# FastDataAcq.net
KiCad netlist of a schematic drawn in EAGLE
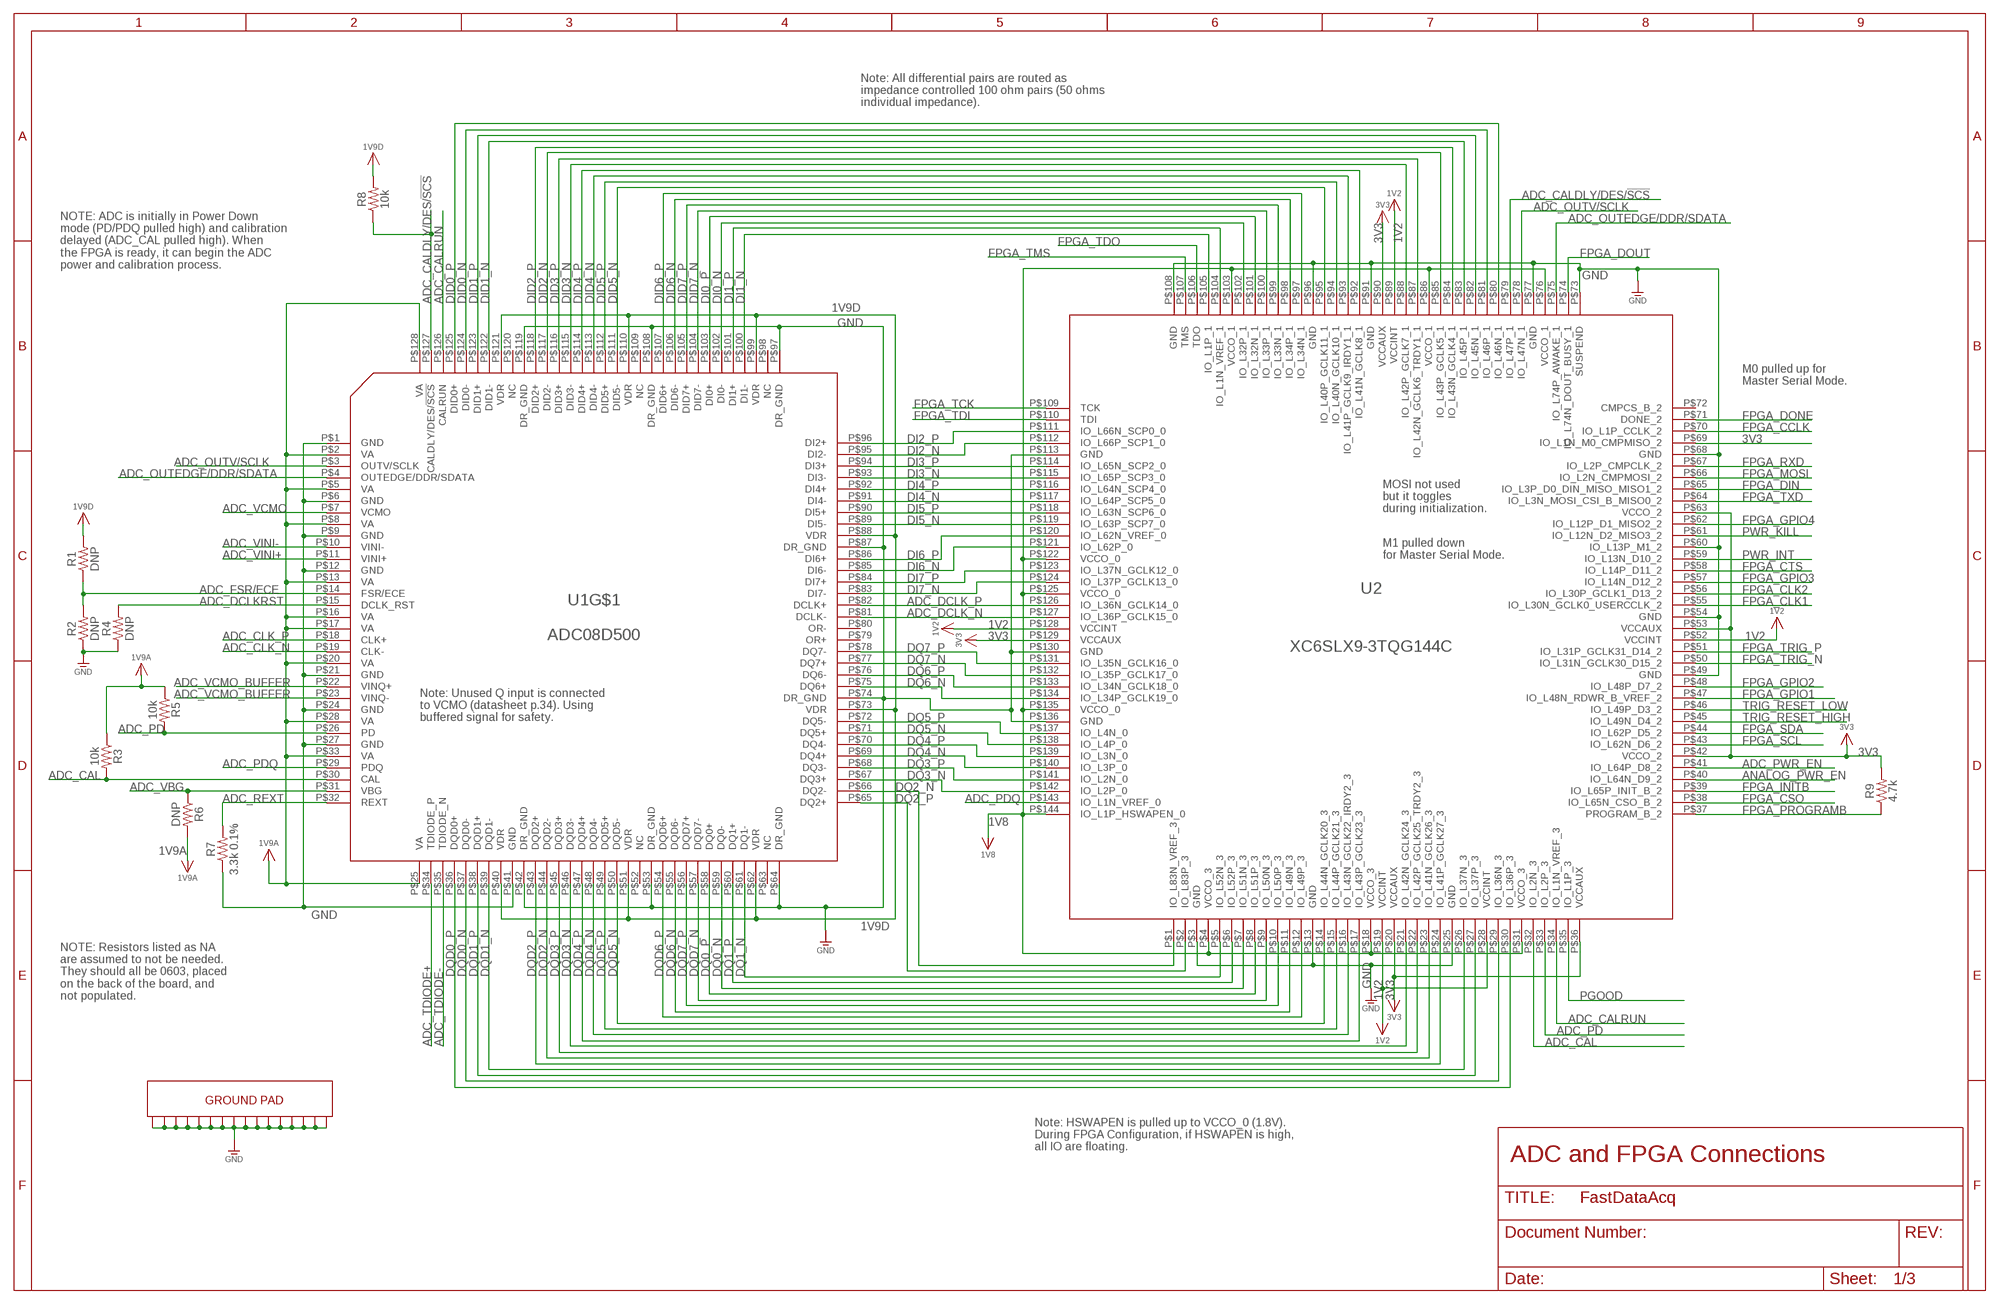
[diagram p0: schematic, sheet 1]
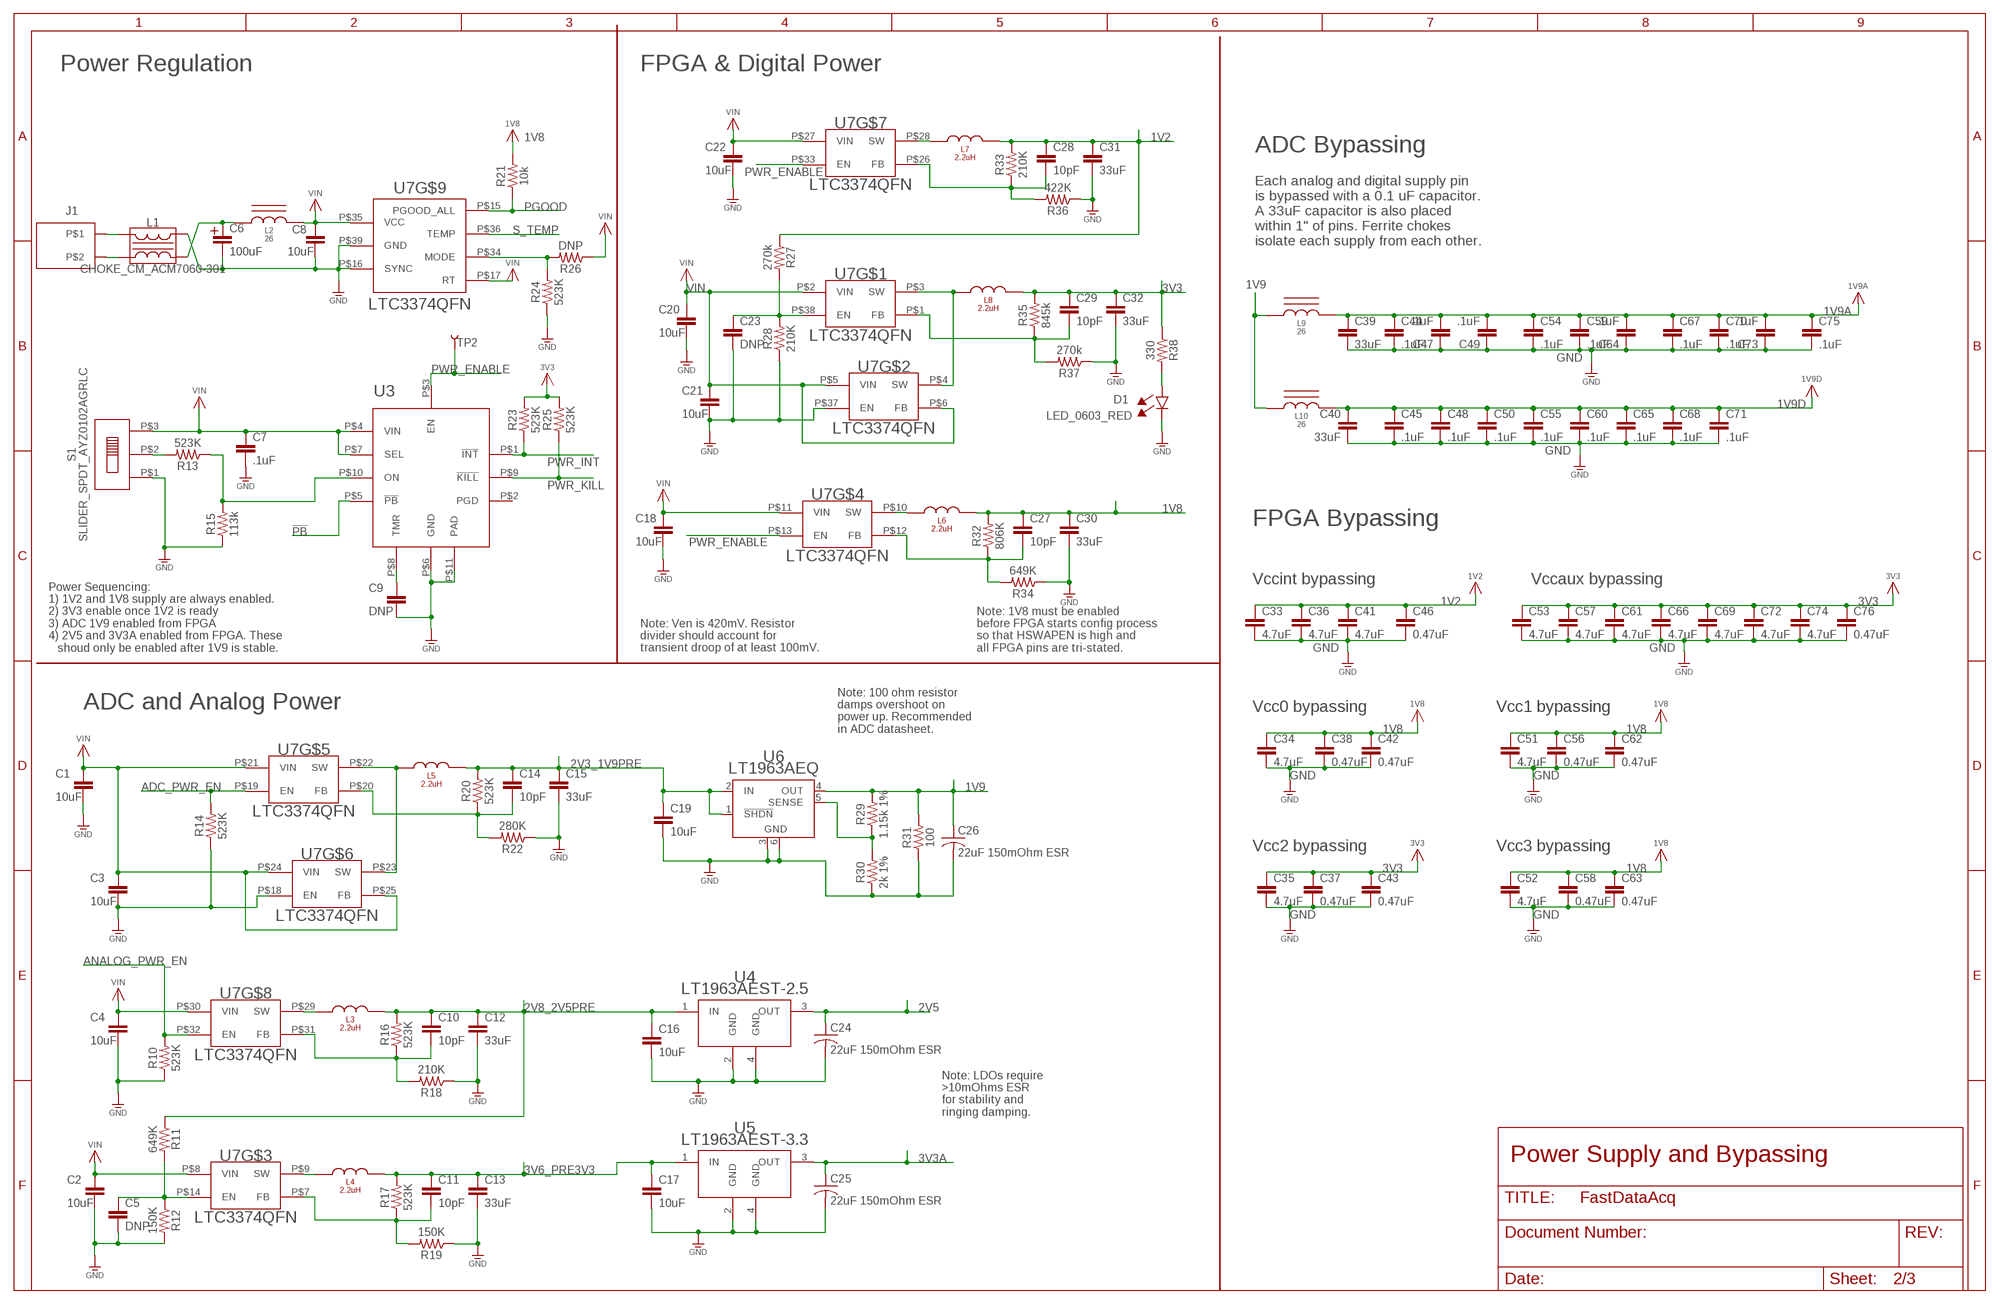
[diagram p1: schematic, sheet 2]
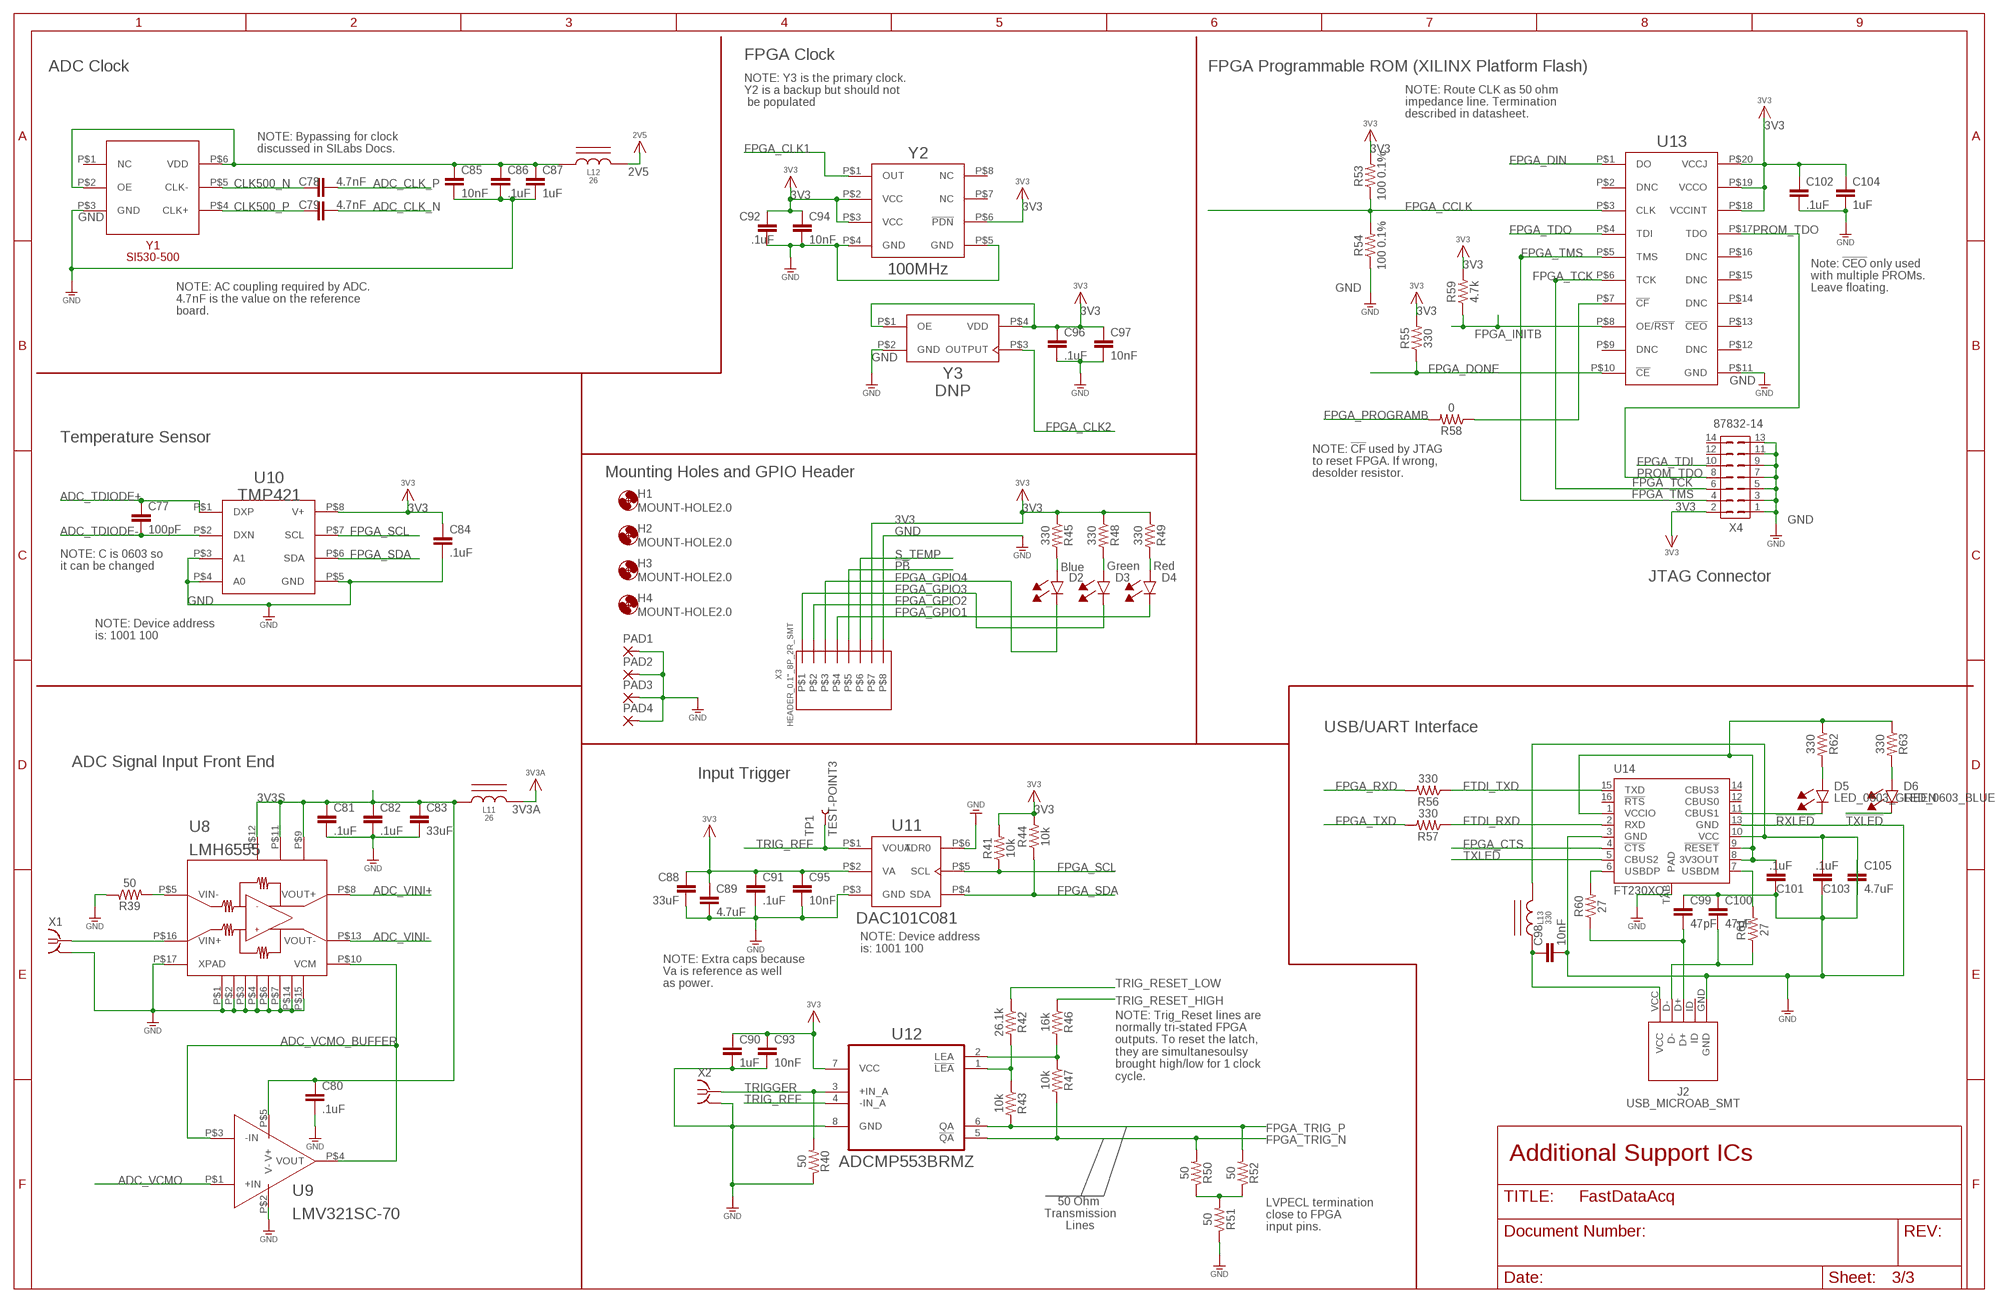
[diagram p2: schematic, sheet 3]

(export (version "E")
  (design (tool "Eeschema 10.0.6"))
  (components
    (comp (ref "R1")
      (value "DNP")
      (footprint "eagle-import:R0603")
      (libsource (lib "eagle-import") (part "R-US_R0603"))
    )
    (comp (ref "R2")
      (value "DNP")
      (footprint "eagle-import:R0603")
      (libsource (lib "eagle-import") (part "R-US_R0603"))
    )
    (comp (ref "R3")
      (value "10k")
      (footprint "eagle-import:R0201")
      (fields
        (field (name "MANPARTNUMBER") "RC0603J103CS")
        (field (name "MANUFACTURER") "Samsung Electro-Mechanics America, Inc")
        (field (name "PARTNUMBER") "1276-3817-1-ND")
      )
      (libsource (lib "eagle-import") (part "R-US_R0201"))
    )
    (comp (ref "R4")
      (value "DNP")
      (footprint "eagle-import:R0603")
      (libsource (lib "eagle-import") (part "R-US_R0603"))
    )
    (comp (ref "R5")
      (value "10k")
      (footprint "eagle-import:R0201")
      (fields
        (field (name "MANPARTNUMBER") "RC0603J103CS")
        (field (name "MANUFACTURER") "Samsung Electro-Mechanics America, Inc")
        (field (name "PARTNUMBER") "1276-3817-1-ND")
      )
      (libsource (lib "eagle-import") (part "R-US_R0201"))
    )
    (comp (ref "R6")
      (value "DNP")
      (footprint "eagle-import:R0603")
      (libsource (lib "eagle-import") (part "R-US_R0603"))
    )
    (comp (ref "R7")
      (value "3.3k 0.1%")
      (footprint "eagle-import:R0603")
      (fields (field (name "PARTNUMBER") "P3.3KDBCT-ND"))
      (libsource (lib "eagle-import") (part "R-US_R0603"))
    )
    (comp (ref "R8")
      (value "10k")
      (footprint "eagle-import:R0201")
      (fields
        (field (name "MANPARTNUMBER") "RC0603J103CS")
        (field (name "MANUFACTURER") "Samsung Electro-Mechanics America, Inc")
        (field (name "PARTNUMBER") "1276-3817-1-ND")
      )
      (libsource (lib "eagle-import") (part "R-US_R0201"))
    )
    (comp (ref "R9")
      (value "4.7k")
      (footprint "eagle-import:R0201")
      (fields
        (field (name "MANPARTNUMBER") "ERJ-1GNJ472C")
        (field (name "MANUFACTURER") "Panasonic Electronic Components")
        (field (name "PARTNUMBER") "P4.7AECT-ND")
      )
      (libsource (lib "eagle-import") (part "R-US_R0201"))
    )
    (comp (ref "U1")
      (value "ADC08D500")
      (footprint "eagle-import:128HLQFP")
      (fields
        (field (name "MANPARTNUMBER") "ADC08D500CIYB/NOPB")
        (field (name "MANUFACTURER") "Texas Instruments")
        (field (name "PARTNUMBER") "ADC08D500CIYB/NOPB-ND")
        (field (name "PARTNUMBER_1") "ADC08D500CIYB/NOPB-ND")
        (field (name "SUPPLIER") "DIGIKEY")
      )
      (libsource (lib "eagle-import") (part "ADC08D500"))
    )
    (comp (ref "U2")
      (value "XC6SLX9-3TQG144C")
      (footprint "eagle-import:TQG144")
      (fields (field (name "MANUFACTURER") "Xilinx Inc") (field (name "PARTNUMBER") "122-1747-ND"))
      (libsource (lib "eagle-import") (part "XC6SLX9-3TQG144C"))
    )
    (comp (ref "C1")
      (value "10uF")
      (footprint "eagle-import:C0603")
      (fields (field (name "PARTNUMBER") "445-4112-1-ND"))
      (libsource (lib "eagle-import") (part "C-EUC0603"))
    )
    (comp (ref "C2")
      (value "10uF")
      (footprint "eagle-import:C0603")
      (fields (field (name "PARTNUMBER") "445-4112-1-ND"))
      (libsource (lib "eagle-import") (part "C-EUC0603"))
    )
    (comp (ref "C3")
      (value "10uF")
      (footprint "eagle-import:C0603")
      (fields (field (name "PARTNUMBER") "445-4112-1-ND"))
      (libsource (lib "eagle-import") (part "C-EUC0603"))
    )
    (comp (ref "C4")
      (value "10uF")
      (footprint "eagle-import:C0603")
      (fields (field (name "PARTNUMBER") "445-4112-1-ND"))
      (libsource (lib "eagle-import") (part "C-EUC0603"))
    )
    (comp (ref "C5")
      (value "DNP")
      (footprint "eagle-import:C0603")
      (libsource (lib "eagle-import") (part "C-EUC0603"))
    )
    (comp (ref "C6")
      (value "100uF")
      (footprint "eagle-import:2917_MURATA_CAP")
      (fields
        (field (name "MANUFACTURER") "Murata Electronics North America")
        (field (name "MANPARTNUMBER") "ECASD91B107M012K00")
        (field (name "PARTNUMBER") "490-5480-1-ND")
      )
      (libsource (lib "eagle-import") (part "CAP_POL_D9_SERIES"))
    )
    (comp (ref "C7")
      (value ".1uF")
      (footprint "eagle-import:0204REVERSE")
      (fields (field (name "PARTNUMBER") "587-2152-1-ND") (field (name "SUPPLIER") "DIGIKEY"))
      (libsource (lib "eagle-import") (part "CAPACITOR0204_REVERSE"))
    )
    (comp (ref "C8")
      (value "10uF")
      (footprint "eagle-import:C0603")
      (fields (field (name "PARTNUMBER") "445-4112-1-ND"))
      (libsource (lib "eagle-import") (part "C-EUC0603"))
    )
    (comp (ref "C9")
      (value "DNP")
      (footprint "eagle-import:C0603")
      (libsource (lib "eagle-import") (part "C-EUC0603"))
    )
    (comp (ref "C10")
      (value "10pF")
      (footprint "eagle-import:C0201")
      (fields (field (name "PARTNUMBER") "445-1769-1-ND"))
      (libsource (lib "eagle-import") (part "C-EUC0201"))
    )
    (comp (ref "C11")
      (value "10pF")
      (footprint "eagle-import:C0201")
      (fields (field (name "PARTNUMBER") "445-1769-1-ND"))
      (libsource (lib "eagle-import") (part "C-EUC0201"))
    )
    (comp (ref "C12")
      (value "33uF")
      (footprint "eagle-import:0805")
      (fields (field (name "PARTNUMBER") "445-8238-1-ND"))
      (libsource (lib "eagle-import") (part "CAP0805"))
    )
    (comp (ref "C13")
      (value "33uF")
      (footprint "eagle-import:0805")
      (fields (field (name "PARTNUMBER") "445-8238-1-ND"))
      (libsource (lib "eagle-import") (part "CAP0805"))
    )
    (comp (ref "C14")
      (value "10pF")
      (footprint "eagle-import:C0201")
      (fields (field (name "PARTNUMBER") "445-1769-1-ND"))
      (libsource (lib "eagle-import") (part "C-EUC0201"))
    )
    (comp (ref "C15")
      (value "33uF")
      (footprint "eagle-import:0805")
      (fields (field (name "PARTNUMBER") "445-8238-1-ND"))
      (libsource (lib "eagle-import") (part "CAP0805"))
    )
    (comp (ref "C16")
      (value "10uF")
      (footprint "eagle-import:C0603")
      (fields (field (name "PARTNUMBER") "445-4112-1-ND"))
      (libsource (lib "eagle-import") (part "C-EUC0603"))
    )
    (comp (ref "C17")
      (value "10uF")
      (footprint "eagle-import:C0603")
      (fields (field (name "PARTNUMBER") "445-4112-1-ND"))
      (libsource (lib "eagle-import") (part "C-EUC0603"))
    )
    (comp (ref "C18")
      (value "10uF")
      (footprint "eagle-import:C0603")
      (fields (field (name "PARTNUMBER") "445-4112-1-ND"))
      (libsource (lib "eagle-import") (part "C-EUC0603"))
    )
    (comp (ref "C19")
      (value "10uF")
      (footprint "eagle-import:C0603")
      (fields (field (name "PARTNUMBER") "445-4112-1-ND"))
      (libsource (lib "eagle-import") (part "C-EUC0603"))
    )
    (comp (ref "C20")
      (value "10uF")
      (footprint "eagle-import:C0603")
      (fields (field (name "PARTNUMBER") "445-4112-1-ND"))
      (libsource (lib "eagle-import") (part "C-EUC0603"))
    )
    (comp (ref "C21")
      (value "10uF")
      (footprint "eagle-import:C0603")
      (fields (field (name "PARTNUMBER") "445-4112-1-ND"))
      (libsource (lib "eagle-import") (part "C-EUC0603"))
    )
    (comp (ref "C22")
      (value "10uF")
      (footprint "eagle-import:C0603")
      (fields (field (name "PARTNUMBER") "445-4112-1-ND"))
      (libsource (lib "eagle-import") (part "C-EUC0603"))
    )
    (comp (ref "C23")
      (value "DNP")
      (footprint "eagle-import:C0603")
      (libsource (lib "eagle-import") (part "C-EUC0603"))
    )
    (comp (ref "C24")
      (value "22uF 150mOhm ESR")
      (footprint "eagle-import:C0805")
      (fields (field (name "PARTNUMBER") "P16231CT-ND"))
      (libsource (lib "eagle-import") (part "C-USC0805"))
    )
    (comp (ref "C25")
      (value "22uF 150mOhm ESR")
      (footprint "eagle-import:C0805")
      (fields (field (name "PARTNUMBER") "P16231CT-ND"))
      (libsource (lib "eagle-import") (part "C-USC0805"))
    )
    (comp (ref "C26")
      (value "22uF 150mOhm ESR")
      (footprint "eagle-import:C0805")
      (fields (field (name "PARTNUMBER") "P16231CT-ND"))
      (libsource (lib "eagle-import") (part "C-USC0805"))
    )
    (comp (ref "C27")
      (value "10pF")
      (footprint "eagle-import:C0201")
      (fields (field (name "PARTNUMBER") "445-1769-1-ND"))
      (libsource (lib "eagle-import") (part "C-EUC0201"))
    )
    (comp (ref "C28")
      (value "10pF")
      (footprint "eagle-import:C0201")
      (fields (field (name "PARTNUMBER") "445-1769-1-ND"))
      (libsource (lib "eagle-import") (part "C-EUC0201"))
    )
    (comp (ref "C29")
      (value "10pF")
      (footprint "eagle-import:C0201")
      (fields (field (name "PARTNUMBER") "445-1769-1-ND"))
      (libsource (lib "eagle-import") (part "C-EUC0201"))
    )
    (comp (ref "C30")
      (value "33uF")
      (footprint "eagle-import:0805")
      (fields (field (name "PARTNUMBER") "445-8238-1-ND"))
      (libsource (lib "eagle-import") (part "CAP0805"))
    )
    (comp (ref "C31")
      (value "33uF")
      (footprint "eagle-import:0805")
      (fields (field (name "PARTNUMBER") "445-8238-1-ND"))
      (libsource (lib "eagle-import") (part "CAP0805"))
    )
    (comp (ref "C32")
      (value "33uF")
      (footprint "eagle-import:0805")
      (fields (field (name "PARTNUMBER") "445-8238-1-ND"))
      (libsource (lib "eagle-import") (part "CAP0805"))
    )
    (comp (ref "C33")
      (value "4.7uF")
      (footprint "eagle-import:0402_C")
      (fields
        (field (name "MANPARTNUMBER") "CL05A475MQ5NRNC")
        (field (name "MANUFACTURER") "Samsung Electro-Mechanics America, Inc")
        (field (name "PARTNUMBER") "1276-1056-1-ND")
      )
      (libsource (lib "eagle-import") (part "CAPACITOR"))
    )
    (comp (ref "C34")
      (value "4.7uF")
      (footprint "eagle-import:0402_C")
      (fields
        (field (name "MANPARTNUMBER") "CL05A475MQ5NRNC")
        (field (name "MANUFACTURER") "Samsung Electro-Mechanics America, Inc")
        (field (name "PARTNUMBER") "1276-1056-1-ND")
      )
      (libsource (lib "eagle-import") (part "CAPACITOR"))
    )
    (comp (ref "C35")
      (value "4.7uF")
      (footprint "eagle-import:0402_C")
      (fields
        (field (name "MANPARTNUMBER") "CL05A475MQ5NRNC")
        (field (name "MANUFACTURER") "Samsung Electro-Mechanics America, Inc")
        (field (name "PARTNUMBER") "1276-1056-1-ND")
      )
      (libsource (lib "eagle-import") (part "CAPACITOR"))
    )
    (comp (ref "C36")
      (value "4.7uF")
      (footprint "eagle-import:0402_C")
      (fields
        (field (name "MANPARTNUMBER") "CL05A475MQ5NRNC")
        (field (name "MANUFACTURER") "Samsung Electro-Mechanics America, Inc")
        (field (name "PARTNUMBER") "1276-1056-1-ND")
      )
      (libsource (lib "eagle-import") (part "CAPACITOR"))
    )
    (comp (ref "C37")
      (value "0.47uF")
      (footprint "eagle-import:0204REVERSE")
      (fields (field (name "PARTNUMBER") "1276-1779-1-ND") (field (name "SUPPLIER") "DIGIKEY"))
      (libsource (lib "eagle-import") (part "CAPACITOR0204_REVERSE"))
    )
    (comp (ref "C38")
      (value "0.47uF")
      (footprint "eagle-import:0204REVERSE")
      (fields (field (name "PARTNUMBER") "1276-1779-1-ND") (field (name "SUPPLIER") "DIGIKEY"))
      (libsource (lib "eagle-import") (part "CAPACITOR0204_REVERSE"))
    )
    (comp (ref "C39")
      (value "33uF")
      (footprint "eagle-import:0805")
      (fields (field (name "PARTNUMBER") "445-8238-1-ND"))
      (libsource (lib "eagle-import") (part "CAP0805"))
    )
    (comp (ref "C40")
      (value "33uF")
      (footprint "eagle-import:0805")
      (fields (field (name "PARTNUMBER") "445-8238-1-ND"))
      (libsource (lib "eagle-import") (part "CAP0805"))
    )
    (comp (ref "C41")
      (value "4.7uF")
      (footprint "eagle-import:0402_C")
      (fields
        (field (name "MANPARTNUMBER") "CL05A475MQ5NRNC")
        (field (name "MANUFACTURER") "Samsung Electro-Mechanics America, Inc")
        (field (name "PARTNUMBER") "1276-1056-1-ND")
      )
      (libsource (lib "eagle-import") (part "CAPACITOR"))
    )
    (comp (ref "C42")
      (value "0.47uF")
      (footprint "eagle-import:0204REVERSE")
      (fields (field (name "PARTNUMBER") "1276-1779-1-ND") (field (name "SUPPLIER") "DIGIKEY"))
      (libsource (lib "eagle-import") (part "CAPACITOR0204_REVERSE"))
    )
    (comp (ref "C43")
      (value "0.47uF")
      (footprint "eagle-import:0204REVERSE")
      (fields (field (name "PARTNUMBER") "1276-1779-1-ND") (field (name "SUPPLIER") "DIGIKEY"))
      (libsource (lib "eagle-import") (part "CAPACITOR0204_REVERSE"))
    )
    (comp (ref "C44")
      (value ".1uF")
      (footprint "eagle-import:0204REVERSE")
      (fields (field (name "PARTNUMBER") "587-2152-1-ND") (field (name "SUPPLIER") "DIGIKEY"))
      (libsource (lib "eagle-import") (part "CAPACITOR0204_REVERSE"))
    )
    (comp (ref "C45")
      (value ".1uF")
      (footprint "eagle-import:0204REVERSE")
      (fields (field (name "PARTNUMBER") "587-2152-1-ND") (field (name "SUPPLIER") "DIGIKEY"))
      (libsource (lib "eagle-import") (part "CAPACITOR0204_REVERSE"))
    )
    (comp (ref "C46")
      (value "0.47uF")
      (footprint "eagle-import:0204REVERSE")
      (fields (field (name "PARTNUMBER") "1276-1779-1-ND") (field (name "SUPPLIER") "DIGIKEY"))
      (libsource (lib "eagle-import") (part "CAPACITOR0204_REVERSE"))
    )
    (comp (ref "C47")
      (value ".1uF")
      (footprint "eagle-import:0204REVERSE")
      (fields (field (name "PARTNUMBER") "587-2152-1-ND") (field (name "SUPPLIER") "DIGIKEY"))
      (libsource (lib "eagle-import") (part "CAPACITOR0204_REVERSE"))
    )
    (comp (ref "C48")
      (value ".1uF")
      (footprint "eagle-import:0204REVERSE")
      (fields (field (name "PARTNUMBER") "587-2152-1-ND") (field (name "SUPPLIER") "DIGIKEY"))
      (libsource (lib "eagle-import") (part "CAPACITOR0204_REVERSE"))
    )
    (comp (ref "C49")
      (value ".1uF")
      (footprint "eagle-import:0204REVERSE")
      (fields (field (name "PARTNUMBER") "587-2152-1-ND") (field (name "SUPPLIER") "DIGIKEY"))
      (libsource (lib "eagle-import") (part "CAPACITOR0204_REVERSE"))
    )
    (comp (ref "C50")
      (value ".1uF")
      (footprint "eagle-import:0204REVERSE")
      (fields (field (name "PARTNUMBER") "587-2152-1-ND") (field (name "SUPPLIER") "DIGIKEY"))
      (libsource (lib "eagle-import") (part "CAPACITOR0204_REVERSE"))
    )
    (comp (ref "C51")
      (value "4.7uF")
      (footprint "eagle-import:0402_C")
      (fields
        (field (name "MANPARTNUMBER") "CL05A475MQ5NRNC")
        (field (name "MANUFACTURER") "Samsung Electro-Mechanics America, Inc")
        (field (name "PARTNUMBER") "1276-1056-1-ND")
      )
      (libsource (lib "eagle-import") (part "CAPACITOR"))
    )
    (comp (ref "C52")
      (value "4.7uF")
      (footprint "eagle-import:0402_C")
      (fields
        (field (name "MANPARTNUMBER") "CL05A475MQ5NRNC")
        (field (name "MANUFACTURER") "Samsung Electro-Mechanics America, Inc")
        (field (name "PARTNUMBER") "1276-1056-1-ND")
      )
      (libsource (lib "eagle-import") (part "CAPACITOR"))
    )
    (comp (ref "C53")
      (value "4.7uF")
      (footprint "eagle-import:0402_C")
      (fields
        (field (name "MANPARTNUMBER") "CL05A475MQ5NRNC")
        (field (name "MANUFACTURER") "Samsung Electro-Mechanics America, Inc")
        (field (name "PARTNUMBER") "1276-1056-1-ND")
      )
      (libsource (lib "eagle-import") (part "CAPACITOR"))
    )
    (comp (ref "C54")
      (value ".1uF")
      (footprint "eagle-import:0204REVERSE")
      (fields (field (name "PARTNUMBER") "587-2152-1-ND") (field (name "SUPPLIER") "DIGIKEY"))
      (libsource (lib "eagle-import") (part "CAPACITOR0204_REVERSE"))
    )
    (comp (ref "C55")
      (value ".1uF")
      (footprint "eagle-import:0204REVERSE")
      (fields (field (name "PARTNUMBER") "587-2152-1-ND") (field (name "SUPPLIER") "DIGIKEY"))
      (libsource (lib "eagle-import") (part "CAPACITOR0204_REVERSE"))
    )
    (comp (ref "C56")
      (value "0.47uF")
      (footprint "eagle-import:0204REVERSE")
      (fields (field (name "PARTNUMBER") "1276-1779-1-ND") (field (name "SUPPLIER") "DIGIKEY"))
      (libsource (lib "eagle-import") (part "CAPACITOR0204_REVERSE"))
    )
    (comp (ref "C57")
      (value "4.7uF")
      (footprint "eagle-import:0402_C")
      (fields
        (field (name "MANPARTNUMBER") "CL05A475MQ5NRNC")
        (field (name "MANUFACTURER") "Samsung Electro-Mechanics America, Inc")
        (field (name "PARTNUMBER") "1276-1056-1-ND")
      )
      (libsource (lib "eagle-import") (part "CAPACITOR"))
    )
    (comp (ref "C58")
      (value "0.47uF")
      (footprint "eagle-import:0204REVERSE")
      (fields (field (name "PARTNUMBER") "1276-1779-1-ND") (field (name "SUPPLIER") "DIGIKEY"))
      (libsource (lib "eagle-import") (part "CAPACITOR0204_REVERSE"))
    )
    (comp (ref "C59")
      (value ".1uF")
      (footprint "eagle-import:0204REVERSE")
      (fields (field (name "PARTNUMBER") "587-2152-1-ND") (field (name "SUPPLIER") "DIGIKEY"))
      (libsource (lib "eagle-import") (part "CAPACITOR0204_REVERSE"))
    )
    (comp (ref "C60")
      (value ".1uF")
      (footprint "eagle-import:0204REVERSE")
      (fields (field (name "PARTNUMBER") "587-2152-1-ND") (field (name "SUPPLIER") "DIGIKEY"))
      (libsource (lib "eagle-import") (part "CAPACITOR0204_REVERSE"))
    )
    (comp (ref "C61")
      (value "4.7uF")
      (footprint "eagle-import:0402_C")
      (fields
        (field (name "MANPARTNUMBER") "CL05A475MQ5NRNC")
        (field (name "MANUFACTURER") "Samsung Electro-Mechanics America, Inc")
        (field (name "PARTNUMBER") "1276-1056-1-ND")
      )
      (libsource (lib "eagle-import") (part "CAPACITOR"))
    )
    (comp (ref "C62")
      (value "0.47uF")
      (footprint "eagle-import:0204REVERSE")
      (fields (field (name "PARTNUMBER") "1276-1779-1-ND") (field (name "SUPPLIER") "DIGIKEY"))
      (libsource (lib "eagle-import") (part "CAPACITOR0204_REVERSE"))
    )
    (comp (ref "C63")
      (value "0.47uF")
      (footprint "eagle-import:0204REVERSE")
      (fields (field (name "PARTNUMBER") "1276-1779-1-ND") (field (name "SUPPLIER") "DIGIKEY"))
      (libsource (lib "eagle-import") (part "CAPACITOR0204_REVERSE"))
    )
    (comp (ref "C64")
      (value ".1uF")
      (footprint "eagle-import:0204REVERSE")
      (fields (field (name "PARTNUMBER") "587-2152-1-ND") (field (name "SUPPLIER") "DIGIKEY"))
      (libsource (lib "eagle-import") (part "CAPACITOR0204_REVERSE"))
    )
    (comp (ref "C65")
      (value ".1uF")
      (footprint "eagle-import:0204REVERSE")
      (fields (field (name "PARTNUMBER") "587-2152-1-ND") (field (name "SUPPLIER") "DIGIKEY"))
      (libsource (lib "eagle-import") (part "CAPACITOR0204_REVERSE"))
    )
    (comp (ref "C66")
      (value "4.7uF")
      (footprint "eagle-import:0402_C")
      (fields
        (field (name "MANPARTNUMBER") "CL05A475MQ5NRNC")
        (field (name "MANUFACTURER") "Samsung Electro-Mechanics America, Inc")
        (field (name "PARTNUMBER") "1276-1056-1-ND")
      )
      (libsource (lib "eagle-import") (part "CAPACITOR"))
    )
    (comp (ref "C67")
      (value ".1uF")
      (footprint "eagle-import:0204REVERSE")
      (fields (field (name "PARTNUMBER") "587-2152-1-ND") (field (name "SUPPLIER") "DIGIKEY"))
      (libsource (lib "eagle-import") (part "CAPACITOR0204_REVERSE"))
    )
    (comp (ref "C68")
      (value ".1uF")
      (footprint "eagle-import:0204REVERSE")
      (fields (field (name "PARTNUMBER") "587-2152-1-ND") (field (name "SUPPLIER") "DIGIKEY"))
      (libsource (lib "eagle-import") (part "CAPACITOR0204_REVERSE"))
    )
    (comp (ref "C69")
      (value "4.7uF")
      (footprint "eagle-import:0402_C")
      (fields
        (field (name "MANPARTNUMBER") "CL05A475MQ5NRNC")
        (field (name "MANUFACTURER") "Samsung Electro-Mechanics America, Inc")
        (field (name "PARTNUMBER") "1276-1056-1-ND")
      )
      (libsource (lib "eagle-import") (part "CAPACITOR"))
    )
    (comp (ref "C70")
      (value ".1uF")
      (footprint "eagle-import:0204REVERSE")
      (fields (field (name "PARTNUMBER") "587-2152-1-ND") (field (name "SUPPLIER") "DIGIKEY"))
      (libsource (lib "eagle-import") (part "CAPACITOR0204_REVERSE"))
    )
    (comp (ref "C71")
      (value ".1uF")
      (footprint "eagle-import:0204REVERSE")
      (fields (field (name "PARTNUMBER") "587-2152-1-ND") (field (name "SUPPLIER") "DIGIKEY"))
      (libsource (lib "eagle-import") (part "CAPACITOR0204_REVERSE"))
    )
    (comp (ref "C72")
      (value "4.7uF")
      (footprint "eagle-import:0402_C")
      (fields
        (field (name "MANPARTNUMBER") "CL05A475MQ5NRNC")
        (field (name "MANUFACTURER") "Samsung Electro-Mechanics America, Inc")
        (field (name "PARTNUMBER") "1276-1056-1-ND")
      )
      (libsource (lib "eagle-import") (part "CAPACITOR"))
    )
    (comp (ref "C73")
      (value ".1uF")
      (footprint "eagle-import:0204REVERSE")
      (fields (field (name "PARTNUMBER") "587-2152-1-ND") (field (name "SUPPLIER") "DIGIKEY"))
      (libsource (lib "eagle-import") (part "CAPACITOR0204_REVERSE"))
    )
    (comp (ref "C74")
      (value "4.7uF")
      (footprint "eagle-import:0402_C")
      (fields
        (field (name "MANPARTNUMBER") "CL05A475MQ5NRNC")
        (field (name "MANUFACTURER") "Samsung Electro-Mechanics America, Inc")
        (field (name "PARTNUMBER") "1276-1056-1-ND")
      )
      (libsource (lib "eagle-import") (part "CAPACITOR"))
    )
    (comp (ref "C75")
      (value ".1uF")
      (footprint "eagle-import:0204REVERSE")
      (fields (field (name "PARTNUMBER") "587-2152-1-ND") (field (name "SUPPLIER") "DIGIKEY"))
      (libsource (lib "eagle-import") (part "CAPACITOR0204_REVERSE"))
    )
    (comp (ref "C76")
      (value "0.47uF")
      (footprint "eagle-import:0204REVERSE")
      (fields (field (name "PARTNUMBER") "1276-1779-1-ND") (field (name "SUPPLIER") "DIGIKEY"))
      (libsource (lib "eagle-import") (part "CAPACITOR0204_REVERSE"))
    )
    (comp (ref "D1")
      (value "LED_0603_RED")
      (footprint "eagle-import:0603_LED")
      (fields
        (field (name "MANPARTNUMBER") "LTST-C193KRKT-5A")
        (field (name "MANUFACTURER") "Lite-On Inc")
        (field (name "PARTNUMBER") "160-1830-1-ND")
        (field (name "PARTNUMBER_1") "LNJ237W82RACT-ND")
      )
      (libsource (lib "eagle-import") (part "LED_0603_RED"))
    )
    (comp (ref "J1")
      (value "MICRO-FIT_3.0_2POS_RA_SMD")
      (footprint "eagle-import:MICRO-FIT_3.02POS_RA_SMD")
      (fields
        (field (name "MANPARTNUMBER") "0436500212")
        (field (name "MANUFACTURER") "Molex Inc")
        (field (name "PARTNUMBER") "WM1890CT-ND")
      )
      (libsource (lib "eagle-import") (part "MICRO-FIT_3.0_2POS_RA_SMD"))
    )
    (comp (ref "L1")
      (value "CHOKE_CM_ACM7060-301")
      (footprint "eagle-import:ACM7060_CHOKE")
      (fields
        (field (name "MANPARTNUMBER") "ACM7060-301-2PL-TL01")
        (field (name "MANUFACTURER") "TDK Corporation")
        (field (name "PARTNUMBER") "445-2214-1-ND")
      )
      (libsource (lib "eagle-import") (part "CHOKE_CM_ACM7060-301"))
    )
    (comp (ref "L2")
      (value "26")
      (footprint "eagle-import:MURATA_BLM18")
      (fields
        (field (name "MANPARTNUMBER") "BLM18SG260TN1D")
        (field (name "MANUFACTURER") "Murata Electronics North America")
        (field (name "PARTNUMBER") "490-3995-1-ND")
      )
      (libsource (lib "eagle-import") (part "FERRITE_BEADS_BLM18SG260"))
    )
    (comp (ref "L3")
      (value "2.2uH")
      (footprint "eagle-import:3.0X3.6_VISHAY")
      (fields (field (name "PARTNUMBER") "541-1322-1-ND") (field (name "SUPPLIER") "DIGIKEY"))
      (libsource (lib "eagle-import") (part "INDUCTOR_3X3.6"))
    )
    (comp (ref "L4")
      (value "2.2uH")
      (footprint "eagle-import:3.0X3.6_VISHAY")
      (fields (field (name "PARTNUMBER") "541-1322-1-ND") (field (name "SUPPLIER") "DIGIKEY"))
      (libsource (lib "eagle-import") (part "INDUCTOR_3X3.6"))
    )
    (comp (ref "L5")
      (value "2.2uH")
      (footprint "eagle-import:5.18X5.49_VISHAY")
      (fields (field (name "PARTNUMBER") "541-1220-1-ND") (field (name "SUPPLIER") "DIGIKEY"))
      (libsource (lib "eagle-import") (part "INDUCTOR_5.18X5.49"))
    )
    (comp (ref "L6")
      (value "2.2uH")
      (footprint "eagle-import:3.0X3.6_VISHAY")
      (fields (field (name "PARTNUMBER") "541-1322-1-ND") (field (name "SUPPLIER") "DIGIKEY"))
      (libsource (lib "eagle-import") (part "INDUCTOR_3X3.6"))
    )
    (comp (ref "L7")
      (value "2.2uH")
      (footprint "eagle-import:3.0X3.6_VISHAY")
      (fields (field (name "PARTNUMBER") "541-1322-1-ND") (field (name "SUPPLIER") "DIGIKEY"))
      (libsource (lib "eagle-import") (part "INDUCTOR_3X3.6"))
    )
    (comp (ref "L8")
      (value "2.2uH")
      (footprint "eagle-import:5.18X5.49_VISHAY")
      (fields (field (name "PARTNUMBER") "541-1220-1-ND") (field (name "SUPPLIER") "DIGIKEY"))
      (libsource (lib "eagle-import") (part "INDUCTOR_5.18X5.49"))
    )
    (comp (ref "L9")
      (value "26")
      (footprint "eagle-import:MURATA_BLM18")
      (fields
        (field (name "MANPARTNUMBER") "BLM18SG260TN1D")
        (field (name "MANUFACTURER") "Murata Electronics North America")
        (field (name "PARTNUMBER") "490-3995-1-ND")
      )
      (libsource (lib "eagle-import") (part "FERRITE_BEADS_BLM18SG260"))
    )
    (comp (ref "L10")
      (value "26")
      (footprint "eagle-import:MURATA_BLM18")
      (fields
        (field (name "MANPARTNUMBER") "BLM18SG260TN1D")
        (field (name "MANUFACTURER") "Murata Electronics North America")
        (field (name "PARTNUMBER") "490-3995-1-ND")
      )
      (libsource (lib "eagle-import") (part "FERRITE_BEADS_BLM18SG260"))
    )
    (comp (ref "R10")
      (value "523K")
      (footprint "eagle-import:R0201")
      (fields (field (name "PARTNUMBER") "P523KABCT-ND"))
      (libsource (lib "eagle-import") (part "R-US_R0201"))
    )
    (comp (ref "R11")
      (value "649K")
      (footprint "eagle-import:R0201")
      (fields (field (name "PARTNUMBER") "P649KABCT-ND"))
      (libsource (lib "eagle-import") (part "R-US_R0201"))
    )
    (comp (ref "R12")
      (value "150K")
      (footprint "eagle-import:R0201")
      (fields (field (name "PARTNUMBER") "1276-3719-1-ND"))
      (libsource (lib "eagle-import") (part "R-US_R0201"))
    )
    (comp (ref "R13")
      (value "523K")
      (footprint "eagle-import:R0201")
      (fields (field (name "PARTNUMBER") "P523KABCT-ND"))
      (libsource (lib "eagle-import") (part "R-US_R0201"))
    )
    (comp (ref "R14")
      (value "523K")
      (footprint "eagle-import:R0201")
      (fields (field (name "PARTNUMBER") "P523KABCT-ND"))
      (libsource (lib "eagle-import") (part "R-US_R0201"))
    )
    (comp (ref "R15")
      (value "113k")
      (footprint "eagle-import:R0201")
      (fields (field (name "PARTNUMBER") "P113KABCT-ND"))
      (libsource (lib "eagle-import") (part "R-US_R0201"))
    )
    (comp (ref "R16")
      (value "523K")
      (footprint "eagle-import:R0201")
      (fields (field (name "PARTNUMBER") "P523KABCT-ND"))
      (libsource (lib "eagle-import") (part "R-US_R0201"))
    )
    (comp (ref "R17")
      (value "523K")
      (footprint "eagle-import:R0201")
      (fields (field (name "PARTNUMBER") "P523KABCT-ND"))
      (libsource (lib "eagle-import") (part "R-US_R0201"))
    )
    (comp (ref "R18")
      (value "210K")
      (footprint "eagle-import:R0201")
      (fields (field (name "PARTNUMBER") "P210KABCT-ND"))
      (libsource (lib "eagle-import") (part "R-US_R0201"))
    )
    (comp (ref "R19")
      (value "150K")
      (footprint "eagle-import:R0201")
      (fields (field (name "PARTNUMBER") "1276-3719-1-ND"))
      (libsource (lib "eagle-import") (part "R-US_R0201"))
    )
    (comp (ref "R20")
      (value "523K")
      (footprint "eagle-import:R0201")
      (fields (field (name "PARTNUMBER") "P523KABCT-ND"))
      (libsource (lib "eagle-import") (part "R-US_R0201"))
    )
    (comp (ref "R21")
      (value "10k")
      (footprint "eagle-import:R0201")
      (fields
        (field (name "MANPARTNUMBER") "RC0603J103CS")
        (field (name "MANUFACTURER") "Samsung Electro-Mechanics America, Inc")
        (field (name "PARTNUMBER") "1276-3817-1-ND")
      )
      (libsource (lib "eagle-import") (part "R-US_R0201"))
    )
    (comp (ref "R22")
      (value "280K")
      (footprint "eagle-import:R0201")
      (fields (field (name "PARTNUMBER") "P280KABCT-ND"))
      (libsource (lib "eagle-import") (part "R-US_R0201"))
    )
    (comp (ref "R23")
      (value "523K")
      (footprint "eagle-import:R0201")
      (fields (field (name "PARTNUMBER") "P523KABCT-ND"))
      (libsource (lib "eagle-import") (part "R-US_R0201"))
    )
    (comp (ref "R24")
      (value "523K")
      (footprint "eagle-import:R0201")
      (fields (field (name "PARTNUMBER") "P523KABCT-ND"))
      (libsource (lib "eagle-import") (part "R-US_R0201"))
    )
    (comp (ref "R25")
      (value "523K")
      (footprint "eagle-import:R0201")
      (fields (field (name "PARTNUMBER") "P523KABCT-ND"))
      (libsource (lib "eagle-import") (part "R-US_R0201"))
    )
    (comp (ref "R26")
      (value "DNP")
      (footprint "eagle-import:R0603")
      (libsource (lib "eagle-import") (part "R-US_R0603"))
    )
    (comp (ref "R27")
      (value "270k")
      (footprint "eagle-import:R0201")
      (fields (field (name "PARTNUMBER") "P270KABCT-ND"))
      (libsource (lib "eagle-import") (part "R-US_R0201"))
    )
    (comp (ref "R28")
      (value "210K")
      (footprint "eagle-import:R0201")
      (fields (field (name "PARTNUMBER") "P210KABCT-ND"))
      (libsource (lib "eagle-import") (part "R-US_R0201"))
    )
    (comp (ref "R29")
      (value "1.15k 1%")
      (footprint "eagle-import:R0603")
      (fields
        (field (name "MANPARTNUMBER") "RC1608F1151CS")
        (field (name "MANUFACTURER") "Samsung Electro-Mechanics America, Inc")
        (field (name "PARTNUMBER") "1276-4649-1-ND")
      )
      (libsource (lib "eagle-import") (part "R-US_R0603"))
    )
    (comp (ref "R30")
      (value "2k 1%")
      (footprint "eagle-import:R0603")
      (fields
        (field (name "MANPARTNUMBER") "RC1608F202CS")
        (field (name "MANUFACTURER") "Samsung Electro-Mechanics America, Inc")
        (field (name "PARTNUMBER") "1276-3495-1-ND")
      )
      (libsource (lib "eagle-import") (part "R-US_R0603"))
    )
    (comp (ref "R31")
      (value "100")
      (footprint "eagle-import:R0603")
      (fields
        (field (name "MANPARTNUMBER") "RC1608J101CS")
        (field (name "MANUFACTURER") "Samsung Electro-Mechanics America, Inc")
        (field (name "PARTNUMBER") "1276-5038-1-ND")
      )
      (libsource (lib "eagle-import") (part "R-US_R0603"))
    )
    (comp (ref "R32")
      (value "806K")
      (footprint "eagle-import:R0201")
      (fields (field (name "PARTNUMBER") "P806KABCT-ND"))
      (libsource (lib "eagle-import") (part "R-US_R0201"))
    )
    (comp (ref "R33")
      (value "210K")
      (footprint "eagle-import:R0201")
      (fields (field (name "PARTNUMBER") "P210KABCT-ND"))
      (libsource (lib "eagle-import") (part "R-US_R0201"))
    )
    (comp (ref "R34")
      (value "649K")
      (footprint "eagle-import:R0201")
      (fields (field (name "PARTNUMBER") "P649KABCT-ND"))
      (libsource (lib "eagle-import") (part "R-US_R0201"))
    )
    (comp (ref "R35")
      (value "845k")
      (footprint "eagle-import:R0201")
      (fields (field (name "PARTNUMBER") "P845KABCT-ND"))
      (libsource (lib "eagle-import") (part "R-US_R0201"))
    )
    (comp (ref "R36")
      (value "422K")
      (footprint "eagle-import:R0201")
      (fields (field (name "PARTNUMBER") "P442KABCT-ND"))
      (libsource (lib "eagle-import") (part "R-US_R0201"))
    )
    (comp (ref "R37")
      (value "270k")
      (footprint "eagle-import:R0201")
      (fields (field (name "PARTNUMBER") "P270KABCT-ND"))
      (libsource (lib "eagle-import") (part "R-US_R0201"))
    )
    (comp (ref "R38")
      (value "330")
      (footprint "eagle-import:R0201")
      (fields
        (field (name "MANPARTNUMBER") "RC0603J331CS")
        (field (name "MANUFACTURER") "Samsung Electro-Mechanics America, Inc")
        (field (name "PARTNUMBER") "1276-3787-1-ND")
      )
      (libsource (lib "eagle-import") (part "R-US_R0201"))
    )
    (comp (ref "S1")
      (value "SLIDER_SPDT_AYZ0102AGRLC")
      (footprint "eagle-import:AYZ0102AGRLC")
      (fields
        (field (name "MANPARTNUMBER") "AYZ0102AGRLC")
        (field (name "MANUFACTURER") "C&K Components")
        (field (name "PARTNUMBER") "401-2012-1-ND")
      )
      (libsource (lib "eagle-import") (part "SLIDER_SPDT_AYZ0102AGRLC"))
    )
    (comp (ref "TP2")
      (value "TEST-POINT3")
      (footprint "eagle-import:PAD.03X.03")
      (libsource (lib "eagle-import") (part "TEST-POINT3"))
    )
    (comp (ref "U3")
      (value "LTC2955-1")
      (footprint "eagle-import:10-DFN")
      (fields
        (field (name "MANPARTNUMBER") "LTC2955CDDB-1#TRMPBF")
        (field (name "MANUFACTURER") "Linear Technology")
        (field (name "PARTNUMBER") "LTC2955CDDB-1#TRMPBFCT-ND")
      )
      (libsource (lib "eagle-import") (part "LTC2955-1"))
    )
    (comp (ref "U4")
      (value "LT1963AEST-2.5")
      (footprint "eagle-import:SOT223")
      (fields
        (field (name "MANPARTNUMBER") "LT1963AEST-2.5#PBF")
        (field (name "MANUFACTURER") "Linear Technology")
        (field (name "PARTNUMBER") "LT1963AEST-2.5#PBF-ND")
      )
      (libsource (lib "eagle-import") (part "LT1963AEST-2.5"))
    )
    (comp (ref "U5")
      (value "LT1963AEST-3.3")
      (footprint "eagle-import:SOT223")
      (fields
        (field (name "MANPARTNUMBER") "LT1963AEST-3.3#PBF")
        (field (name "MANUFACTURER") "Linear Technology")
        (field (name "PARTNUMBER") "LT1963AEST-3.3#PBF-ND")
      )
      (libsource (lib "eagle-import") (part "LT1963AEST-3.3"))
    )
    (comp (ref "U6")
      (value "LT1963AEQ")
      (footprint "eagle-import:Q5-DD")
      (fields
        (field (name "MANPARTNUMBER") "LT1963AEQ#PBF")
        (field (name "MANUFACTURER") "Linear Technology")
        (field (name "PARTNUMBER") "LT1963AEQ#PBF-ND")
      )
      (libsource (lib "eagle-import") (part "LT1963AEQ"))
    )
    (comp (ref "U7")
      (value "LTC3374QFN")
      (footprint "eagle-import:38-QFN_(5X7)")
      (fields
        (field (name "MANPARTNUMBER") "TC3374EUHF#PBF")
        (field (name "MANUFACTURER") "Linear Technology")
        (field (name "PARTNUMBER") "LTC3374EUHF#PBF-ND")
      )
      (libsource (lib "eagle-import") (part "LTC3374QFN"))
    )
    (comp (ref "C77")
      (value "100pF")
      (footprint "eagle-import:C0201")
      (fields (field (name "PARTNUMBER") "445-4675-1-ND") (field (name "SUPPLIER") "DIGIKEY"))
      (libsource (lib "eagle-import") (part "C-EUC0201"))
    )
    (comp (ref "C78")
      (value "4.7nF")
      (footprint "eagle-import:C0201")
      (fields (field (name "PARTNUMBER") "445-13726-1-ND"))
      (libsource (lib "eagle-import") (part "C-EUC0201"))
    )
    (comp (ref "C79")
      (value "4.7nF")
      (footprint "eagle-import:C0201")
      (fields (field (name "PARTNUMBER") "445-13726-1-ND"))
      (libsource (lib "eagle-import") (part "C-EUC0201"))
    )
    (comp (ref "C80")
      (value ".1uF")
      (footprint "eagle-import:0204REVERSE")
      (fields (field (name "PARTNUMBER") "587-2152-1-ND") (field (name "SUPPLIER") "DIGIKEY"))
      (libsource (lib "eagle-import") (part "CAPACITOR0204_REVERSE"))
    )
    (comp (ref "C81")
      (value ".1uF")
      (footprint "eagle-import:0204REVERSE")
      (fields (field (name "PARTNUMBER") "587-2152-1-ND") (field (name "SUPPLIER") "DIGIKEY"))
      (libsource (lib "eagle-import") (part "CAPACITOR0204_REVERSE"))
    )
    (comp (ref "C82")
      (value ".1uF")
      (footprint "eagle-import:0204REVERSE")
      (fields (field (name "PARTNUMBER") "587-2152-1-ND") (field (name "SUPPLIER") "DIGIKEY"))
      (libsource (lib "eagle-import") (part "CAPACITOR0204_REVERSE"))
    )
    (comp (ref "C83")
      (value "33uF")
      (footprint "eagle-import:0805")
      (fields (field (name "PARTNUMBER") "445-8238-1-ND"))
      (libsource (lib "eagle-import") (part "CAP0805"))
    )
    (comp (ref "C84")
      (value ".1uF")
      (footprint "eagle-import:0204REVERSE")
      (fields (field (name "PARTNUMBER") "587-2152-1-ND") (field (name "SUPPLIER") "DIGIKEY"))
      (libsource (lib "eagle-import") (part "CAPACITOR0204_REVERSE"))
    )
    (comp (ref "C85")
      (value "10nF")
      (footprint "eagle-import:C0201")
      (fields (field (name "PARTNUMBER") "445-1793-1-ND"))
      (libsource (lib "eagle-import") (part "C-EUC0201"))
    )
    (comp (ref "C86")
      (value ".1uF")
      (footprint "eagle-import:0204REVERSE")
      (fields (field (name "PARTNUMBER") "587-2152-1-ND") (field (name "SUPPLIER") "DIGIKEY"))
      (libsource (lib "eagle-import") (part "CAPACITOR0204_REVERSE"))
    )
    (comp (ref "C87")
      (value "1uF")
      (footprint "eagle-import:0204REVERSE")
      (fields (field (name "PARTNUMBER") "445-9091-1-ND") (field (name "SUPPLIER") "DIGIKEY"))
      (libsource (lib "eagle-import") (part "CAPACITOR0204_REVERSE"))
    )
    (comp (ref "C88")
      (value "33uF")
      (footprint "eagle-import:0805")
      (fields (field (name "PARTNUMBER") "445-8238-1-ND"))
      (libsource (lib "eagle-import") (part "CAP0805"))
    )
    (comp (ref "C89")
      (value "4.7uF")
      (footprint "eagle-import:0402_C")
      (fields
        (field (name "MANPARTNUMBER") "CL05A475MQ5NRNC")
        (field (name "MANUFACTURER") "Samsung Electro-Mechanics America, Inc")
        (field (name "PARTNUMBER") "1276-1056-1-ND")
      )
      (libsource (lib "eagle-import") (part "CAPACITOR"))
    )
    (comp (ref "C90")
      (value "1uF")
      (footprint "eagle-import:0204REVERSE")
      (fields (field (name "PARTNUMBER") "445-9091-1-ND") (field (name "SUPPLIER") "DIGIKEY"))
      (libsource (lib "eagle-import") (part "CAPACITOR0204_REVERSE"))
    )
    (comp (ref "C91")
      (value ".1uF")
      (footprint "eagle-import:0204REVERSE")
      (fields (field (name "PARTNUMBER") "587-2152-1-ND") (field (name "SUPPLIER") "DIGIKEY"))
      (libsource (lib "eagle-import") (part "CAPACITOR0204_REVERSE"))
    )
    (comp (ref "C92")
      (value ".1uF")
      (footprint "eagle-import:0204REVERSE")
      (fields (field (name "PARTNUMBER") "587-2152-1-ND") (field (name "SUPPLIER") "DIGIKEY"))
      (libsource (lib "eagle-import") (part "CAPACITOR0204_REVERSE"))
    )
    (comp (ref "C93")
      (value "10nF")
      (footprint "eagle-import:C0201")
      (fields (field (name "PARTNUMBER") "445-1793-1-ND"))
      (libsource (lib "eagle-import") (part "C-EUC0201"))
    )
    (comp (ref "C94")
      (value "10nF")
      (footprint "eagle-import:C0201")
      (fields (field (name "PARTNUMBER") "445-1793-1-ND"))
      (libsource (lib "eagle-import") (part "C-EUC0201"))
    )
    (comp (ref "C95")
      (value "10nF")
      (footprint "eagle-import:C0201")
      (fields (field (name "PARTNUMBER") "445-1793-1-ND"))
      (libsource (lib "eagle-import") (part "C-EUC0201"))
    )
    (comp (ref "C96")
      (value ".1uF")
      (footprint "eagle-import:0204REVERSE")
      (fields (field (name "PARTNUMBER") "587-2152-1-ND") (field (name "SUPPLIER") "DIGIKEY"))
      (libsource (lib "eagle-import") (part "CAPACITOR0204_REVERSE"))
    )
    (comp (ref "C97")
      (value "10nF")
      (footprint "eagle-import:C0201")
      (fields (field (name "PARTNUMBER") "445-1793-1-ND"))
      (libsource (lib "eagle-import") (part "C-EUC0201"))
    )
    (comp (ref "C98")
      (value "10nF")
      (footprint "eagle-import:C0201")
      (fields (field (name "PARTNUMBER") "445-1793-1-ND"))
      (libsource (lib "eagle-import") (part "C-EUC0201"))
    )
    (comp (ref "C99")
      (value "47pF")
      (footprint "eagle-import:C0201")
      (fields (field (name "PARTNUMBER") "445-1782-1-ND"))
      (libsource (lib "eagle-import") (part "C-EUC0201"))
    )
    (comp (ref "C100")
      (value "47pF")
      (footprint "eagle-import:C0201")
      (fields (field (name "PARTNUMBER") "445-1782-1-ND"))
      (libsource (lib "eagle-import") (part "C-EUC0201"))
    )
    (comp (ref "C101")
      (value ".1uF")
      (footprint "eagle-import:0204REVERSE")
      (fields (field (name "PARTNUMBER") "587-2152-1-ND") (field (name "SUPPLIER") "DIGIKEY"))
      (libsource (lib "eagle-import") (part "CAPACITOR0204_REVERSE"))
    )
    (comp (ref "C102")
      (value ".1uF")
      (footprint "eagle-import:0204REVERSE")
      (fields (field (name "PARTNUMBER") "587-2152-1-ND") (field (name "SUPPLIER") "DIGIKEY"))
      (libsource (lib "eagle-import") (part "CAPACITOR0204_REVERSE"))
    )
    (comp (ref "C103")
      (value ".1uF")
      (footprint "eagle-import:0204REVERSE")
      (fields (field (name "PARTNUMBER") "587-2152-1-ND") (field (name "SUPPLIER") "DIGIKEY"))
      (libsource (lib "eagle-import") (part "CAPACITOR0204_REVERSE"))
    )
    (comp (ref "C104")
      (value "1uF")
      (footprint "eagle-import:0204REVERSE")
      (fields (field (name "PARTNUMBER") "445-9091-1-ND") (field (name "SUPPLIER") "DIGIKEY"))
      (libsource (lib "eagle-import") (part "CAPACITOR0204_REVERSE"))
    )
    (comp (ref "C105")
      (value "4.7uF")
      (footprint "eagle-import:0402_C")
      (fields
        (field (name "MANPARTNUMBER") "CL05A475MQ5NRNC")
        (field (name "MANUFACTURER") "Samsung Electro-Mechanics America, Inc")
        (field (name "PARTNUMBER") "1276-1056-1-ND")
      )
      (libsource (lib "eagle-import") (part "CAPACITOR"))
    )
    (comp (ref "D2")
      (value "LED_0603_BLUE")
      (footprint "eagle-import:0603_LED")
      (fields
        (field (name "MANPARTNUMBER") "LTST-C193TBKT-5A")
        (field (name "MANUFACTURER") "Lite-On Inc")
        (field (name "PARTNUMBER") "160-1827-1-ND")
      )
      (libsource (lib "eagle-import") (part "LED_0603_BLUE"))
    )
    (comp (ref "D3")
      (value "LED_0603_GREEN")
      (footprint "eagle-import:0603_LED")
      (fields
        (field (name "MANPARTNUMBER") "LTST-C193KGKT-5A")
        (field (name "MANUFACTURER") "Lite-On Inc")
        (field (name "PARTNUMBER") "160-1828-1-ND")
      )
      (libsource (lib "eagle-import") (part "LED_0603_GREEN"))
    )
    (comp (ref "D4")
      (value "LED_0603_RED")
      (footprint "eagle-import:0603_LED")
      (fields
        (field (name "MANPARTNUMBER") "LTST-C193KRKT-5A")
        (field (name "MANUFACTURER") "Lite-On Inc")
        (field (name "PARTNUMBER") "160-1830-1-ND")
        (field (name "PARTNUMBER_1") "LNJ237W82RACT-ND")
      )
      (libsource (lib "eagle-import") (part "LED_0603_RED"))
    )
    (comp (ref "D5")
      (value "LED_0603_GREEN")
      (footprint "eagle-import:0603_LED")
      (fields
        (field (name "MANPARTNUMBER") "LTST-C193KGKT-5A")
        (field (name "MANUFACTURER") "Lite-On Inc")
        (field (name "PARTNUMBER") "160-1828-1-ND")
      )
      (libsource (lib "eagle-import") (part "LED_0603_GREEN"))
    )
    (comp (ref "D6")
      (value "LED_0603_BLUE")
      (footprint "eagle-import:0603_LED")
      (fields
        (field (name "MANPARTNUMBER") "LTST-C193TBKT-5A")
        (field (name "MANUFACTURER") "Lite-On Inc")
        (field (name "PARTNUMBER") "160-1827-1-ND")
      )
      (libsource (lib "eagle-import") (part "LED_0603_BLUE"))
    )
    (comp (ref "H1")
      (value "MOUNT-HOLE2.0")
      (footprint "eagle-import:2.0")
      (libsource (lib "eagle-import") (part "MOUNT-HOLE2.0"))
    )
    (comp (ref "H2")
      (value "MOUNT-HOLE2.0")
      (footprint "eagle-import:2.0")
      (libsource (lib "eagle-import") (part "MOUNT-HOLE2.0"))
    )
    (comp (ref "H3")
      (value "MOUNT-HOLE2.0")
      (footprint "eagle-import:2.0")
      (libsource (lib "eagle-import") (part "MOUNT-HOLE2.0"))
    )
    (comp (ref "H4")
      (value "MOUNT-HOLE2.0")
      (footprint "eagle-import:2.0")
      (libsource (lib "eagle-import") (part "MOUNT-HOLE2.0"))
    )
    (comp (ref "J2")
      (value "USB_MICROAB_SMT")
      (footprint "eagle-import:USB_MICROAB_SMT_1")
      (fields
        (field (name "MANPARTNUMBER") "10104111-0001LF")
        (field (name "MANUFACTURER") "FCI")
        (field (name "PARTNUMBER") "609-4053-1-ND")
      )
      (libsource (lib "eagle-import") (part "USB_MICROAB_SMT"))
    )
    (comp (ref "L11")
      (value "26")
      (footprint "eagle-import:MURATA_BLM18")
      (fields
        (field (name "MANPARTNUMBER") "BLM18SG260TN1D")
        (field (name "MANUFACTURER") "Murata Electronics North America")
        (field (name "PARTNUMBER") "490-3995-1-ND")
      )
      (libsource (lib "eagle-import") (part "FERRITE_BEADS_BLM18SG260"))
    )
    (comp (ref "L12")
      (value "26")
      (footprint "eagle-import:MURATA_BLM18")
      (fields
        (field (name "MANPARTNUMBER") "BLM18SG260TN1D")
        (field (name "MANUFACTURER") "Murata Electronics North America")
        (field (name "PARTNUMBER") "490-3995-1-ND")
      )
      (libsource (lib "eagle-import") (part "FERRITE_BEADS_BLM18SG260"))
    )
    (comp (ref "L13")
      (value "330")
      (footprint "eagle-import:MURATA_BLM18")
      (fields
        (field (name "MANPARTNUMBER") "BLM18SG331TN1D")
        (field (name "MANUFACTURER") "Murata Electronics North America")
        (field (name "PARTNUMBER") "490-3997-1-ND")
      )
      (libsource (lib "eagle-import") (part "FERRITE_BEADS_BLM18SG331"))
    )
    (comp (ref "PAD1")
      (value "SMD2")
      (footprint "eagle-import:SMD1,27-2,54")
      (libsource (lib "eagle-import") (part "SMD2"))
    )
    (comp (ref "PAD2")
      (value "SMD2")
      (footprint "eagle-import:SMD1,27-2,54")
      (libsource (lib "eagle-import") (part "SMD2"))
    )
    (comp (ref "PAD3")
      (value "SMD2")
      (footprint "eagle-import:SMD1,27-2,54")
      (libsource (lib "eagle-import") (part "SMD2"))
    )
    (comp (ref "PAD4")
      (value "SMD2")
      (footprint "eagle-import:SMD1,27-2,54")
      (libsource (lib "eagle-import") (part "SMD2"))
    )
    (comp (ref "R39")
      (value "50")
      (footprint "eagle-import:R0201")
      (fields
        (field (name "MANPARTNUMBER") "RC0603F49R9C")
        (field (name "MANUFACTURER") "Samsung Electro-Mechanics America, Inc")
        (field (name "PARTNUMBER") "1276-3590-1-ND")
      )
      (libsource (lib "eagle-import") (part "R-US_R0201"))
    )
    (comp (ref "R40")
      (value "50")
      (footprint "eagle-import:R0201")
      (fields
        (field (name "MANPARTNUMBER") "RC0603F49R9C")
        (field (name "MANUFACTURER") "Samsung Electro-Mechanics America, Inc")
        (field (name "PARTNUMBER") "1276-3590-1-ND")
      )
      (libsource (lib "eagle-import") (part "R-US_R0201"))
    )
    (comp (ref "R41")
      (value "10k")
      (footprint "eagle-import:R0201")
      (fields
        (field (name "MANPARTNUMBER") "RC0603J103CS")
        (field (name "MANUFACTURER") "Samsung Electro-Mechanics America, Inc")
        (field (name "PARTNUMBER") "1276-3817-1-ND")
      )
      (libsource (lib "eagle-import") (part "R-US_R0201"))
    )
    (comp (ref "R42")
      (value "26.1k")
      (footprint "eagle-import:R0603")
      (fields (field (name "PARTNUMBER") "1276-4779-1-ND"))
      (libsource (lib "eagle-import") (part "R-US_R0603"))
    )
    (comp (ref "R43")
      (value "10k")
      (footprint "eagle-import:R0201")
      (fields
        (field (name "MANPARTNUMBER") "RC0603J103CS")
        (field (name "MANUFACTURER") "Samsung Electro-Mechanics America, Inc")
        (field (name "PARTNUMBER") "1276-3817-1-ND")
      )
      (libsource (lib "eagle-import") (part "R-US_R0201"))
    )
    (comp (ref "R44")
      (value "10k")
      (footprint "eagle-import:R0201")
      (fields
        (field (name "MANPARTNUMBER") "RC0603J103CS")
        (field (name "MANUFACTURER") "Samsung Electro-Mechanics America, Inc")
        (field (name "PARTNUMBER") "1276-3817-1-ND")
      )
      (libsource (lib "eagle-import") (part "R-US_R0201"))
    )
    (comp (ref "R45")
      (value "330")
      (footprint "eagle-import:R0201")
      (fields
        (field (name "MANPARTNUMBER") "RC0603J331CS")
        (field (name "MANUFACTURER") "Samsung Electro-Mechanics America, Inc")
        (field (name "PARTNUMBER") "1276-3787-1-ND")
      )
      (libsource (lib "eagle-import") (part "R-US_R0201"))
    )
    (comp (ref "R46")
      (value "16k")
      (footprint "eagle-import:R0603")
      (fields (field (name "PARTNUMBER") "1276-5091-1-ND"))
      (libsource (lib "eagle-import") (part "R-US_R0603"))
    )
    (comp (ref "R47")
      (value "10k")
      (footprint "eagle-import:R0201")
      (fields
        (field (name "MANPARTNUMBER") "RC0603J103CS")
        (field (name "MANUFACTURER") "Samsung Electro-Mechanics America, Inc")
        (field (name "PARTNUMBER") "1276-3817-1-ND")
      )
      (libsource (lib "eagle-import") (part "R-US_R0201"))
    )
    (comp (ref "R48")
      (value "330")
      (footprint "eagle-import:R0201")
      (fields
        (field (name "MANPARTNUMBER") "RC0603J331CS")
        (field (name "MANUFACTURER") "Samsung Electro-Mechanics America, Inc")
        (field (name "PARTNUMBER") "1276-3787-1-ND")
      )
      (libsource (lib "eagle-import") (part "R-US_R0201"))
    )
    (comp (ref "R49")
      (value "330")
      (footprint "eagle-import:R0201")
      (fields
        (field (name "MANPARTNUMBER") "RC0603J331CS")
        (field (name "MANUFACTURER") "Samsung Electro-Mechanics America, Inc")
        (field (name "PARTNUMBER") "1276-3787-1-ND")
      )
      (libsource (lib "eagle-import") (part "R-US_R0201"))
    )
    (comp (ref "R50")
      (value "50")
      (footprint "eagle-import:R0201")
      (fields
        (field (name "MANPARTNUMBER") "RC0603F49R9C")
        (field (name "MANUFACTURER") "Samsung Electro-Mechanics America, Inc")
        (field (name "PARTNUMBER") "1276-3590-1-ND")
      )
      (libsource (lib "eagle-import") (part "R-US_R0201"))
    )
    (comp (ref "R51")
      (value "50")
      (footprint "eagle-import:R0201")
      (fields
        (field (name "MANPARTNUMBER") "RC0603F49R9C")
        (field (name "MANUFACTURER") "Samsung Electro-Mechanics America, Inc")
        (field (name "PARTNUMBER") "1276-3590-1-ND")
      )
      (libsource (lib "eagle-import") (part "R-US_R0201"))
    )
    (comp (ref "R52")
      (value "50")
      (footprint "eagle-import:R0201")
      (fields
        (field (name "MANPARTNUMBER") "RC0603F49R9C")
        (field (name "MANUFACTURER") "Samsung Electro-Mechanics America, Inc")
        (field (name "PARTNUMBER") "1276-3590-1-ND")
      )
      (libsource (lib "eagle-import") (part "R-US_R0201"))
    )
    (comp (ref "R53")
      (value "100 0.1%")
      (footprint "eagle-import:R0402")
      (fields
        (field (name "MANPARTNUMBER") "ERA-2AEB101X")
        (field (name "MANUFACTURER") "Panasonic Electronic Components")
        (field (name "PARTNUMBER") "P100DCCT-ND")
      )
      (libsource (lib "eagle-import") (part "R-US_R0402"))
    )
    (comp (ref "R54")
      (value "100 0.1%")
      (footprint "eagle-import:R0402")
      (fields
        (field (name "MANPARTNUMBER") "ERA-2AEB101X")
        (field (name "MANUFACTURER") "Panasonic Electronic Components")
        (field (name "PARTNUMBER") "P100DCCT-ND")
      )
      (libsource (lib "eagle-import") (part "R-US_R0402"))
    )
    (comp (ref "R55")
      (value "330")
      (footprint "eagle-import:R0201")
      (fields
        (field (name "MANPARTNUMBER") "RC0603J331CS")
        (field (name "MANUFACTURER") "Samsung Electro-Mechanics America, Inc")
        (field (name "PARTNUMBER") "1276-3787-1-ND")
      )
      (libsource (lib "eagle-import") (part "R-US_R0201"))
    )
    (comp (ref "R56")
      (value "330")
      (footprint "eagle-import:R0201")
      (fields
        (field (name "MANPARTNUMBER") "RC0603J331CS")
        (field (name "MANUFACTURER") "Samsung Electro-Mechanics America, Inc")
        (field (name "PARTNUMBER") "1276-3787-1-ND")
      )
      (libsource (lib "eagle-import") (part "R-US_R0201"))
    )
    (comp (ref "R57")
      (value "330")
      (footprint "eagle-import:R0201")
      (fields
        (field (name "MANPARTNUMBER") "RC0603J331CS")
        (field (name "MANUFACTURER") "Samsung Electro-Mechanics America, Inc")
        (field (name "PARTNUMBER") "1276-3787-1-ND")
      )
      (libsource (lib "eagle-import") (part "R-US_R0201"))
    )
    (comp (ref "R58")
      (value "0")
      (footprint "eagle-import:R0603")
      (fields (field (name "PARTNUMBER") "311-0.0GRCT-ND"))
      (libsource (lib "eagle-import") (part "R-US_R0603"))
    )
    (comp (ref "R59")
      (value "4.7k")
      (footprint "eagle-import:R0201")
      (fields
        (field (name "MANPARTNUMBER") "ERJ-1GNJ472C")
        (field (name "MANUFACTURER") "Panasonic Electronic Components")
        (field (name "PARTNUMBER") "P4.7AECT-ND")
      )
      (libsource (lib "eagle-import") (part "R-US_R0201"))
    )
    (comp (ref "R60")
      (value "27")
      (footprint "eagle-import:R0201")
      (fields (field (name "PARTNUMBER") "1276-3577-1-ND"))
      (libsource (lib "eagle-import") (part "R-US_R0201"))
    )
    (comp (ref "R61")
      (value "27")
      (footprint "eagle-import:R0201")
      (fields (field (name "PARTNUMBER") "1276-3577-1-ND"))
      (libsource (lib "eagle-import") (part "R-US_R0201"))
    )
    (comp (ref "R62")
      (value "330")
      (footprint "eagle-import:R0201")
      (fields
        (field (name "MANPARTNUMBER") "RC0603J331CS")
        (field (name "MANUFACTURER") "Samsung Electro-Mechanics America, Inc")
        (field (name "PARTNUMBER") "1276-3787-1-ND")
      )
      (libsource (lib "eagle-import") (part "R-US_R0201"))
    )
    (comp (ref "R63")
      (value "330")
      (footprint "eagle-import:R0201")
      (fields
        (field (name "MANPARTNUMBER") "RC0603J331CS")
        (field (name "MANUFACTURER") "Samsung Electro-Mechanics America, Inc")
        (field (name "PARTNUMBER") "1276-3787-1-ND")
      )
      (libsource (lib "eagle-import") (part "R-US_R0201"))
    )
    (comp (ref "TP1")
      (value "TEST-POINT3")
      (footprint "eagle-import:PAD.03X.03")
      (libsource (lib "eagle-import") (part "TEST-POINT3"))
    )
    (comp (ref "U8")
      (value "LMH6555")
      (footprint "eagle-import:16WQFN")
      (fields
        (field (name "MANPARTNUMBER") "LMH6555SQ/NOPB")
        (field (name "MANUFACTURER") "Texas Instruments")
        (field (name "PARTNUMBER") "LMH6555SQ/NOPBCT-ND")
      )
      (libsource (lib "eagle-import") (part "LMH6555"))
    )
    (comp (ref "U9")
      (value "LMV321SC-70")
      (footprint "eagle-import:SC-70")
      (fields
        (field (name "MANPARTNUMBER") "LMV321IDCKR")
        (field (name "MANUFACTURER") "Texas Instruments")
        (field (name "PARTNUMBER") "296-9568-1-ND")
      )
      (libsource (lib "eagle-import") (part "LMV321SC-70"))
    )
    (comp (ref "U10")
      (value "TMP421")
      (footprint "eagle-import:SOT23-8")
      (fields
        (field (name "MANPARTNUMBER") "TMP421AIDCNT")
        (field (name "MANUFACTURER") "Texas Instruments")
        (field (name "PARTNUMBER") "296-21990-1-ND")
      )
      (libsource (lib "eagle-import") (part "TMP421"))
    )
    (comp (ref "U11")
      (value "DAC101C081")
      (footprint "eagle-import:SOT23-6")
      (fields
        (field (name "MANPARTNUMBER") "DAC101C081CIMK/NOPB")
        (field (name "MANUFACTURER") "Texas Instruments")
        (field (name "PARTNUMBER") "DAC101C081CIMK/NOPBCT-ND")
      )
      (libsource (lib "eagle-import") (part "DAC101C081"))
    )
    (comp (ref "U12")
      (value "ADCMP553BRMZ")
      (footprint "eagle-import:SOP65P490X110-8N")
      (fields (field (name "MANUFACTURER") "Analog Devices") (field (name "PARTNUMBER") "ADCMP553BRMZ-ND"))
      (libsource (lib "eagle-import") (part "ADCMP553BRMZ"))
    )
    (comp (ref "U13")
      (value "XCFXXS04")
      (footprint "eagle-import:TSSOP20_XILINX")
      (fields
        (field (name "MANPARTNUMBER") "XCF04SVOG20C")
        (field (name "MANUFACTURER") "Xilinx inc")
        (field (name "PARTNUMBER") "122-1288-5-ND")
      )
      (libsource (lib "eagle-import") (part "XCFXXS04"))
    )
    (comp (ref "U14")
      (value "FT230XQ")
      (footprint "eagle-import:QFN16")
      (fields
        (field (name "MANPARTNUMBER") "FT230XQ-R")
        (field (name "MANUFACTURER") "FTDI")
        (field (name "PARTNUMBER") "768-1130-1-ND")
      )
      (libsource (lib "eagle-import") (part "FT230XQ"))
    )
    (comp (ref "X1")
      (value "SMA-142-0701-801/806")
      (footprint "eagle-import:J502-ND-142-0701-801_806")
      (fields
        (field (name "MF") "JOHNSON COMPONENTS")
        (field (name "MPN") "142-0701-801")
        (field (name "MANUFACTURER") "Emerson Network Power Connectivity Johnson")
      )
      (libsource (lib "eagle-import") (part "SMA-142-0701-801/806"))
    )
    (comp (ref "X2")
      (value "SMA-142-0701-801/806")
      (footprint "eagle-import:J502-ND-142-0701-801_806")
      (fields
        (field (name "MF") "JOHNSON COMPONENTS")
        (field (name "MPN") "142-0701-801")
        (field (name "MANUFACTURER") "Emerson Network Power Connectivity Johnson")
      )
      (libsource (lib "eagle-import") (part "SMA-142-0701-801/806"))
    )
    (comp (ref "X3")
      (value "HEADER_0.1\"_8P_2R_SMT")
      (footprint "eagle-import:HEADER_8P_2R_SMT")
      (fields
        (field (name "MANPARTNUMBER") "0015912080")
        (field (name "MANUFACTURER") "Molex Inc")
        (field (name "PARTNUMBER") "WM17450-ND")
      )
      (libsource (lib "eagle-import") (part "HEADER_0.1{dblquote}_8P_2R_SMT"))
    )
    (comp (ref "X4")
      (value "87832-14")
      (footprint "eagle-import:87832-14")
      (fields
        (field (name "MANPARTNUMBER") "0878321420")
        (field (name "MANUFACTURER") "Molex Inc")
        (field (name "PARTNUMBER") "WM18641-ND")
      )
      (libsource (lib "eagle-import") (part "87832-14"))
    )
    (comp (ref "Y1")
      (value "SI530-500")
      (footprint "eagle-import:SI530")
      (fields (field (name "PARTNUMBER") "530FC500M000DG"))
      (libsource (lib "eagle-import") (part "SI530-500"))
    )
    (comp (ref "Y2")
      (value "100MHz")
      (footprint "eagle-import:UMAX8")
      (fields
        (field (name "MANPARTNUMBER") "DS1088LU-100+")
        (field (name "MANUFACTURER") "Maxim Integrated")
        (field (name "PARTNUMBER") "DS1088LU-100+-ND")
      )
      (libsource (lib "eagle-import") (part "DS1088L_100MHZ"))
    )
    (comp (ref "Y3")
      (value "DNP")
      (footprint "eagle-import:SI500S")
      (fields
        (field (name "MANPARTNUMBER") "500SAAA-ACF")
        (field (name "MANUFACTURER") "Silicon Laboratories Inc")
        (field (name "PARTNUMBER") "500SAAA-ACF-ND")
      )
      (libsource (lib "eagle-import") (part "SI500S"))
    )
  )
  (nets
    (net (code "1") (name "1V2") (class "Default")
      (node (ref "C28") (pin "1") (pinfunction "1_1") (pintype "passive"))
      (node (ref "C31") (pin "1") (pinfunction "1_1") (pintype "passive"))
      (node (ref "C33") (pin "P$1") (pinfunction "1_P$1") (pintype "passive"))
      (node (ref "C36") (pin "P$1") (pinfunction "1_P$1") (pintype "passive"))
      (node (ref "C41") (pin "P$1") (pinfunction "1_P$1") (pintype "passive"))
      (node (ref "C46") (pin "P$1") (pinfunction "1_P$1") (pintype "passive"))
      (node (ref "L7") (pin "P$2") (pinfunction "P$2_P$2") (pintype "bidirectional"))
      (node (ref "R27") (pin "1") (pinfunction "1_1") (pintype "passive"))
      (node (ref "R33") (pin "2") (pinfunction "2_2") (pintype "passive"))
      (node (ref "U2") (pin "P$128") (pinfunction "VCCINT_P$128") (pintype "power_in"))
      (node (ref "U2") (pin "P$19") (pinfunction "VCCINT_P$19") (pintype "power_in"))
      (node (ref "U2") (pin "P$28") (pinfunction "VCCINT_P$28") (pintype "power_in"))
      (node (ref "U2") (pin "P$52") (pinfunction "VCCINT_P$52") (pintype "power_in"))
      (node (ref "U2") (pin "P$89") (pinfunction "VCCINT_P$89") (pintype "power_in"))
    )
    (net (code "2") (name "1V8") (class "Default")
      (node (ref "C27") (pin "1") (pinfunction "1_1") (pintype "passive"))
      (node (ref "C30") (pin "1") (pinfunction "1_1") (pintype "passive"))
      (node (ref "C34") (pin "P$1") (pinfunction "1_P$1") (pintype "passive"))
      (node (ref "C38") (pin "P$1") (pinfunction "1_P$1") (pintype "passive"))
      (node (ref "C42") (pin "P$1") (pinfunction "1_P$1") (pintype "passive"))
      (node (ref "C51") (pin "P$1") (pinfunction "1_P$1") (pintype "passive"))
      (node (ref "C52") (pin "P$1") (pinfunction "1_P$1") (pintype "passive"))
      (node (ref "C56") (pin "P$1") (pinfunction "1_P$1") (pintype "passive"))
      (node (ref "C58") (pin "P$1") (pinfunction "1_P$1") (pintype "passive"))
      (node (ref "C62") (pin "P$1") (pinfunction "1_P$1") (pintype "passive"))
      (node (ref "C63") (pin "P$1") (pinfunction "1_P$1") (pintype "passive"))
      (node (ref "L6") (pin "P$2") (pinfunction "P$2_P$2") (pintype "bidirectional"))
      (node (ref "R21") (pin "2") (pinfunction "2_2") (pintype "passive"))
      (node (ref "R32") (pin "2") (pinfunction "2_2") (pintype "passive"))
      (node (ref "U2") (pin "P$103") (pinfunction "VCCO_1_P$103") (pintype "power_in"))
      (node (ref "U2") (pin "P$122") (pinfunction "VCCO_0_P$122") (pintype "power_in"))
      (node (ref "U2") (pin "P$125") (pinfunction "VCCO_0_P$125") (pintype "power_in"))
      (node (ref "U2") (pin "P$135") (pinfunction "VCCO_0_P$135") (pintype "power_in"))
      (node (ref "U2") (pin "P$144") (pinfunction "IO_L1P_HSWAPEN_0_P$144") (pintype "bidirectional"))
      (node (ref "U2") (pin "P$18") (pinfunction "VCCO_3_P$18") (pintype "power_in"))
      (node (ref "U2") (pin "P$31") (pinfunction "VCCO_3_P$31") (pintype "power_in"))
      (node (ref "U2") (pin "P$4") (pinfunction "VCCO_3_P$4") (pintype "power_in"))
      (node (ref "U2") (pin "P$76") (pinfunction "VCCO_1_P$76") (pintype "power_in"))
      (node (ref "U2") (pin "P$86") (pinfunction "VCCO_1_P$86") (pintype "power_in"))
    )
    (net (code "3") (name "1V9") (class "Default")
      (node (ref "C26") (pin "1") (pinfunction "1_1") (pintype "passive"))
      (node (ref "L10") (pin "P$1") (pinfunction "P$1_P$1") (pintype "bidirectional"))
      (node (ref "L9") (pin "P$1") (pinfunction "P$1_P$1") (pintype "bidirectional"))
      (node (ref "R29") (pin "2") (pinfunction "2_2") (pintype "passive"))
      (node (ref "R31") (pin "2") (pinfunction "2_2") (pintype "passive"))
      (node (ref "U6") (pin "4") (pinfunction "OUT_4") (pintype "passive"))
    )
    (net (code "4") (name "1V9A") (class "Default")
      (node (ref "C39") (pin "1") (pinfunction "1_1") (pintype "passive"))
      (node (ref "C44") (pin "P$1") (pinfunction "1_P$1") (pintype "passive"))
      (node (ref "C47") (pin "P$2") (pinfunction "2_P$2") (pintype "passive"))
      (node (ref "C49") (pin "P$2") (pinfunction "2_P$2") (pintype "passive"))
      (node (ref "C54") (pin "P$1") (pinfunction "1_P$1") (pintype "passive"))
      (node (ref "C59") (pin "P$1") (pinfunction "1_P$1") (pintype "passive"))
      (node (ref "C64") (pin "P$2") (pinfunction "2_P$2") (pintype "passive"))
      (node (ref "C67") (pin "P$1") (pinfunction "1_P$1") (pintype "passive"))
      (node (ref "C70") (pin "P$1") (pinfunction "1_P$1") (pintype "passive"))
      (node (ref "C73") (pin "P$2") (pinfunction "2_P$2") (pintype "passive"))
      (node (ref "C75") (pin "P$1") (pinfunction "1_P$1") (pintype "passive"))
      (node (ref "L9") (pin "P$2") (pinfunction "P$2_P$2") (pintype "bidirectional"))
      (node (ref "R3") (pin "1") (pinfunction "1_1") (pintype "passive"))
      (node (ref "R5") (pin "1") (pinfunction "1_1") (pintype "passive"))
      (node (ref "R6") (pin "2") (pinfunction "2_2") (pintype "passive"))
      (node (ref "U1") (pin "P$128") (pinfunction "VA_P$128") (pintype "passive"))
      (node (ref "U1") (pin "P$13") (pinfunction "VA_P$13") (pintype "passive"))
      (node (ref "U1") (pin "P$16") (pinfunction "VA_P$16") (pintype "passive"))
      (node (ref "U1") (pin "P$17") (pinfunction "VA_P$17") (pintype "passive"))
      (node (ref "U1") (pin "P$2") (pinfunction "VA_P$2") (pintype "passive"))
      (node (ref "U1") (pin "P$20") (pinfunction "VA_P$20") (pintype "passive"))
      (node (ref "U1") (pin "P$25") (pinfunction "VA_P$25") (pintype "passive"))
      (node (ref "U1") (pin "P$28") (pinfunction "VA_P$28") (pintype "passive"))
      (node (ref "U1") (pin "P$33") (pinfunction "VA_P$33") (pintype "passive"))
      (node (ref "U1") (pin "P$5") (pinfunction "VA_P$5") (pintype "passive"))
      (node (ref "U1") (pin "P$8") (pinfunction "VA_P$8") (pintype "passive"))
    )
    (net (code "5") (name "1V9D") (class "Default")
      (node (ref "C40") (pin "1") (pinfunction "1_1") (pintype "passive"))
      (node (ref "C45") (pin "P$1") (pinfunction "1_P$1") (pintype "passive"))
      (node (ref "C48") (pin "P$1") (pinfunction "1_P$1") (pintype "passive"))
      (node (ref "C50") (pin "P$1") (pinfunction "1_P$1") (pintype "passive"))
      (node (ref "C55") (pin "P$1") (pinfunction "1_P$1") (pintype "passive"))
      (node (ref "C60") (pin "P$1") (pinfunction "1_P$1") (pintype "passive"))
      (node (ref "C65") (pin "P$1") (pinfunction "1_P$1") (pintype "passive"))
      (node (ref "C68") (pin "P$1") (pinfunction "1_P$1") (pintype "passive"))
      (node (ref "C71") (pin "P$1") (pinfunction "1_P$1") (pintype "passive"))
      (node (ref "L10") (pin "P$2") (pinfunction "P$2_P$2") (pintype "bidirectional"))
      (node (ref "R1") (pin "2") (pinfunction "2_2") (pintype "passive"))
      (node (ref "R8") (pin "2") (pinfunction "2_2") (pintype "passive"))
      (node (ref "U1") (pin "P$110") (pinfunction "VDR_P$110") (pintype "passive"))
      (node (ref "U1") (pin "P$121") (pinfunction "VDR_P$121") (pintype "passive"))
      (node (ref "U1") (pin "P$40") (pinfunction "VDR_P$40") (pintype "passive"))
      (node (ref "U1") (pin "P$51") (pinfunction "VDR_P$51") (pintype "passive"))
      (node (ref "U1") (pin "P$62") (pinfunction "VDR_P$62") (pintype "passive"))
      (node (ref "U1") (pin "P$73") (pinfunction "VDR_P$73") (pintype "passive"))
      (node (ref "U1") (pin "P$88") (pinfunction "VDR_P$88") (pintype "passive"))
      (node (ref "U1") (pin "P$99") (pinfunction "VDR_P$99") (pintype "passive"))
    )
    (net (code "6") (name "2V3_1V9PRE") (class "Default")
      (node (ref "C14") (pin "1") (pinfunction "1_1") (pintype "passive"))
      (node (ref "C15") (pin "1") (pinfunction "1_1") (pintype "passive"))
      (node (ref "C19") (pin "1") (pinfunction "1_1") (pintype "passive"))
      (node (ref "L5") (pin "P$2") (pinfunction "P$2_P$2") (pintype "bidirectional"))
      (node (ref "R20") (pin "2") (pinfunction "2_2") (pintype "passive"))
      (node (ref "U6") (pin "1") (pinfunction "~{SHDN}_1") (pintype "input"))
      (node (ref "U6") (pin "2") (pinfunction "IN_2") (pintype "input"))
    )
    (net (code "7") (name "2V5") (class "Default")
      (node (ref "C24") (pin "1") (pinfunction "1_1") (pintype "passive"))
      (node (ref "L12") (pin "P$2") (pinfunction "P$2_P$2") (pintype "bidirectional"))
      (node (ref "U4") (pin "3") (pinfunction "OUT_3") (pintype "power_in"))
    )
    (net (code "8") (name "2V8_2V5PRE") (class "Default")
      (node (ref "C10") (pin "1") (pinfunction "1_1") (pintype "passive"))
      (node (ref "C12") (pin "1") (pinfunction "1_1") (pintype "passive"))
      (node (ref "C16") (pin "1") (pinfunction "1_1") (pintype "passive"))
      (node (ref "L3") (pin "P$2") (pinfunction "P$2_P$2") (pintype "bidirectional"))
      (node (ref "R11") (pin "1") (pinfunction "1_1") (pintype "passive"))
      (node (ref "R16") (pin "2") (pinfunction "2_2") (pintype "passive"))
      (node (ref "U4") (pin "1") (pinfunction "IN_1") (pintype "power_in"))
    )
    (net (code "9") (name "3V3") (class "Default")
      (node (ref "C102") (pin "P$1") (pinfunction "1_P$1") (pintype "passive"))
      (node (ref "C104") (pin "P$1") (pinfunction "1_P$1") (pintype "passive"))
      (node (ref "C29") (pin "1") (pinfunction "1_1") (pintype "passive"))
      (node (ref "C32") (pin "1") (pinfunction "1_1") (pintype "passive"))
      (node (ref "C35") (pin "P$1") (pinfunction "1_P$1") (pintype "passive"))
      (node (ref "C37") (pin "P$1") (pinfunction "1_P$1") (pintype "passive"))
      (node (ref "C43") (pin "P$1") (pinfunction "1_P$1") (pintype "passive"))
      (node (ref "C53") (pin "P$1") (pinfunction "1_P$1") (pintype "passive"))
      (node (ref "C57") (pin "P$1") (pinfunction "1_P$1") (pintype "passive"))
      (node (ref "C61") (pin "P$1") (pinfunction "1_P$1") (pintype "passive"))
      (node (ref "C66") (pin "P$1") (pinfunction "1_P$1") (pintype "passive"))
      (node (ref "C69") (pin "P$1") (pinfunction "1_P$1") (pintype "passive"))
      (node (ref "C72") (pin "P$1") (pinfunction "1_P$1") (pintype "passive"))
      (node (ref "C74") (pin "P$1") (pinfunction "1_P$1") (pintype "passive"))
      (node (ref "C76") (pin "P$1") (pinfunction "1_P$1") (pintype "passive"))
      (node (ref "C84") (pin "P$1") (pinfunction "1_P$1") (pintype "passive"))
      (node (ref "C88") (pin "1") (pinfunction "1_1") (pintype "passive"))
      (node (ref "C89") (pin "P$1") (pinfunction "1_P$1") (pintype "passive"))
      (node (ref "C90") (pin "P$1") (pinfunction "1_P$1") (pintype "passive"))
      (node (ref "C91") (pin "P$1") (pinfunction "1_P$1") (pintype "passive"))
      (node (ref "C92") (pin "P$1") (pinfunction "1_P$1") (pintype "passive"))
      (node (ref "C93") (pin "1") (pinfunction "1_1") (pintype "passive"))
      (node (ref "C94") (pin "1") (pinfunction "1_1") (pintype "passive"))
      (node (ref "C95") (pin "1") (pinfunction "1_1") (pintype "passive"))
      (node (ref "C96") (pin "P$1") (pinfunction "1_P$1") (pintype "passive"))
      (node (ref "C97") (pin "1") (pinfunction "1_1") (pintype "passive"))
      (node (ref "L8") (pin "P$2") (pinfunction "P$2_P$2") (pintype "bidirectional"))
      (node (ref "R23") (pin "2") (pinfunction "2_2") (pintype "passive"))
      (node (ref "R25") (pin "2") (pinfunction "2_2") (pintype "passive"))
      (node (ref "R35") (pin "2") (pinfunction "2_2") (pintype "passive"))
      (node (ref "R38") (pin "1") (pinfunction "1_1") (pintype "passive"))
      (node (ref "R41") (pin "2") (pinfunction "2_2") (pintype "passive"))
      (node (ref "R44") (pin "2") (pinfunction "2_2") (pintype "passive"))
      (node (ref "R45") (pin "1") (pinfunction "1_1") (pintype "passive"))
      (node (ref "R48") (pin "1") (pinfunction "1_1") (pintype "passive"))
      (node (ref "R49") (pin "1") (pinfunction "1_1") (pintype "passive"))
      (node (ref "R53") (pin "2") (pinfunction "2_2") (pintype "passive"))
      (node (ref "R55") (pin "2") (pinfunction "2_2") (pintype "passive"))
      (node (ref "R59") (pin "2") (pinfunction "2_2") (pintype "passive"))
      (node (ref "R9") (pin "2") (pinfunction "2_2") (pintype "passive"))
      (node (ref "U10") (pin "P$8") (pinfunction "V+_P$8") (pintype "power_in"))
      (node (ref "U11") (pin "P$2") (pinfunction "VA_P$2") (pintype "power_in"))
      (node (ref "U12") (pin "7") (pinfunction "VCC_7") (pintype "power_in"))
      (node (ref "U13") (pin "P$18") (pinfunction "VCCINT_P$18") (pintype "power_in"))
      (node (ref "U13") (pin "P$19") (pinfunction "VCCO_P$19") (pintype "power_in"))
      (node (ref "U13") (pin "P$20") (pinfunction "VCCJ_P$20") (pintype "power_in"))
      (node (ref "U2") (pin "P$129") (pinfunction "VCCAUX_P$129") (pintype "power_in"))
      (node (ref "U2") (pin "P$20") (pinfunction "VCCAUX_P$20") (pintype "power_in"))
      (node (ref "U2") (pin "P$36") (pinfunction "VCCAUX_P$36") (pintype "power_in"))
      (node (ref "U2") (pin "P$42") (pinfunction "VCCO_2_P$42") (pintype "power_in"))
      (node (ref "U2") (pin "P$53") (pinfunction "VCCAUX_P$53") (pintype "power_in"))
      (node (ref "U2") (pin "P$63") (pinfunction "VCCO_2_P$63") (pintype "power_in"))
      (node (ref "U2") (pin "P$69") (pinfunction "IO_L1N_M0_CMPMISO_2_P$69") (pintype "bidirectional"))
      (node (ref "U2") (pin "P$90") (pinfunction "VCCAUX_P$90") (pintype "power_in"))
      (node (ref "X3") (pin "P$7") (pinfunction "P$7_P$7") (pintype "bidirectional"))
      (node (ref "X4") (pin "2") (pinfunction "2_2") (pintype "passive"))
      (node (ref "Y2") (pin "P$2") (pinfunction "VCC_P$2") (pintype "power_in"))
      (node (ref "Y2") (pin "P$3") (pinfunction "VCC_P$3") (pintype "power_in"))
      (node (ref "Y2") (pin "P$6") (pinfunction "~{PDN}_P$6") (pintype "input"))
      (node (ref "Y3") (pin "P$1") (pinfunction "OE_P$1") (pintype "input"))
      (node (ref "Y3") (pin "P$4") (pinfunction "VDD_P$4") (pintype "power_in"))
    )
    (net (code "10") (name "3V3A") (class "Default")
      (node (ref "C25") (pin "1") (pinfunction "1_1") (pintype "passive"))
      (node (ref "L11") (pin "P$2") (pinfunction "P$2_P$2") (pintype "bidirectional"))
      (node (ref "U5") (pin "3") (pinfunction "OUT_3") (pintype "power_in"))
    )
    (net (code "11") (name "3V3S") (class "Default")
      (node (ref "C80") (pin "P$1") (pinfunction "1_P$1") (pintype "passive"))
      (node (ref "C81") (pin "P$1") (pinfunction "1_P$1") (pintype "passive"))
      (node (ref "C82") (pin "P$1") (pinfunction "1_P$1") (pintype "passive"))
      (node (ref "C83") (pin "1") (pinfunction "1_1") (pintype "passive"))
      (node (ref "L11") (pin "P$1") (pinfunction "P$1_P$1") (pintype "bidirectional"))
      (node (ref "U8") (pin "P$11") (pinfunction "VCC_P$11") (pintype "power_in"))
      (node (ref "U8") (pin "P$12") (pinfunction "VCC_P$12") (pintype "power_in"))
      (node (ref "U8") (pin "P$9") (pinfunction "VCC_P$9") (pintype "power_in"))
      (node (ref "U9") (pin "P$5") (pinfunction "V+_P$5") (pintype "power_in"))
    )
    (net (code "12") (name "3V6_PRE3V3") (class "Default")
      (node (ref "C11") (pin "1") (pinfunction "1_1") (pintype "passive"))
      (node (ref "C13") (pin "1") (pinfunction "1_1") (pintype "passive"))
      (node (ref "C17") (pin "1") (pinfunction "1_1") (pintype "passive"))
      (node (ref "L4") (pin "P$2") (pinfunction "P$2_P$2") (pintype "bidirectional"))
      (node (ref "R17") (pin "2") (pinfunction "2_2") (pintype "passive"))
      (node (ref "U5") (pin "1") (pinfunction "IN_1") (pintype "power_in"))
    )
    (net (code "13") (name "ADC_CAL") (class "Default")
      (node (ref "R3") (pin "2") (pinfunction "2_2") (pintype "passive"))
      (node (ref "U1") (pin "P$30") (pinfunction "CAL_P$30") (pintype "input"))
      (node (ref "U2") (pin "P$32") (pinfunction "IO_L2N_3_P$32") (pintype "bidirectional"))
    )
    (net (code "14") (name "ADC_CALDLY{slash}DES{slash}~{SCS}") (class "Default")
      (node (ref "R8") (pin "1") (pinfunction "1_1") (pintype "passive"))
      (node (ref "U1") (pin "P$127") (pinfunction "CALDLY/DES/~{SCS}_P$127") (pintype "input"))
      (node (ref "U2") (pin "P$79") (pinfunction "IO_L47P_1_P$79") (pintype "bidirectional"))
    )
    (net (code "15") (name "ADC_CALRUN") (class "Default")
      (node (ref "U1") (pin "P$126") (pinfunction "CALRUN_P$126") (pintype "output"))
      (node (ref "U2") (pin "P$34") (pinfunction "IO_L1N_VREF_3_P$34") (pintype "bidirectional"))
    )
    (net (code "16") (name "ADC_CLK_N") (class "Default")
      (node (ref "C79") (pin "2") (pinfunction "2_2") (pintype "passive"))
      (node (ref "U1") (pin "P$19") (pinfunction "CLK-_P$19") (pintype "input"))
    )
    (net (code "17") (name "ADC_CLK_P") (class "Default")
      (node (ref "C78") (pin "2") (pinfunction "2_2") (pintype "passive"))
      (node (ref "U1") (pin "P$18") (pinfunction "CLK+_P$18") (pintype "input"))
    )
    (net (code "18") (name "ADC_DCLKRST") (class "Default")
      (node (ref "R4") (pin "2") (pinfunction "2_2") (pintype "passive"))
      (node (ref "U1") (pin "P$15") (pinfunction "DCLK_RST_P$15") (pintype "input"))
    )
    (net (code "19") (name "ADC_DCLK_N") (class "Default")
      (node (ref "U1") (pin "P$81") (pinfunction "DCLK-_P$81") (pintype "output"))
      (node (ref "U2") (pin "P$127") (pinfunction "IO_L36P_GCLK15_0_P$127") (pintype "bidirectional"))
    )
    (net (code "20") (name "ADC_DCLK_P") (class "Default")
      (node (ref "U1") (pin "P$82") (pinfunction "DCLK+_P$82") (pintype "output"))
      (node (ref "U2") (pin "P$126") (pinfunction "IO_L36N_GCLK14_0_P$126") (pintype "bidirectional"))
    )
    (net (code "21") (name "ADC_FSR{slash}ECE") (class "Default")
      (node (ref "R1") (pin "1") (pinfunction "1_1") (pintype "passive"))
      (node (ref "R2") (pin "2") (pinfunction "2_2") (pintype "passive"))
      (node (ref "U1") (pin "P$14") (pinfunction "FSR/ECE_P$14") (pintype "input"))
    )
    (net (code "22") (name "ADC_OUTEDGE{slash}DDR{slash}SDATA") (class "Default")
      (node (ref "U1") (pin "P$4") (pinfunction "OUTEDGE/DDR/SDATA_P$4") (pintype "input"))
      (node (ref "U2") (pin "P$75") (pinfunction "IO_L74P_AWAKE_1_P$75") (pintype "bidirectional"))
    )
    (net (code "23") (name "ADC_OUTV{slash}SCLK") (class "Default")
      (node (ref "U1") (pin "P$3") (pinfunction "OUTV/SCLK_P$3") (pintype "input"))
      (node (ref "U2") (pin "P$78") (pinfunction "IO_L47N_1_P$78") (pintype "bidirectional"))
    )
    (net (code "24") (name "ADC_PD") (class "Default")
      (node (ref "R5") (pin "2") (pinfunction "2_2") (pintype "passive"))
      (node (ref "U1") (pin "P$26") (pinfunction "PD_P$26") (pintype "input"))
      (node (ref "U2") (pin "P$33") (pinfunction "IO_L2P_3_P$33") (pintype "bidirectional"))
    )
    (net (code "25") (name "ADC_PDQ") (class "Default")
      (node (ref "U1") (pin "P$29") (pinfunction "PDQ_P$29") (pintype "input"))
      (node (ref "U2") (pin "P$143") (pinfunction "IO_L1N_VREF_0_P$143") (pintype "bidirectional"))
    )
    (net (code "26") (name "ADC_PWR_EN") (class "Default")
      (node (ref "R14") (pin "2") (pinfunction "2_2") (pintype "passive"))
      (node (ref "U2") (pin "P$41") (pinfunction "IO_L64P_D8_2_P$41") (pintype "bidirectional"))
      (node (ref "U7") (pin "P$19") (pinfunction "EN_P$19") (pintype "input"))
    )
    (net (code "27") (name "ADC_REXT") (class "Default")
      (node (ref "R7") (pin "2") (pinfunction "2_2") (pintype "passive"))
      (node (ref "U1") (pin "P$32") (pinfunction "REXT_P$32") (pintype "output"))
    )
    (net (code "28") (name "ADC_TDIODE+") (class "Default")
      (node (ref "C77") (pin "1") (pinfunction "1_1") (pintype "passive"))
      (node (ref "U1") (pin "P$34") (pinfunction "TDIODE_P_P$34") (pintype "bidirectional"))
      (node (ref "U10") (pin "P$1") (pinfunction "DXP_P$1") (pintype "bidirectional"))
    )
    (net (code "29") (name "ADC_TDIODE-") (class "Default")
      (node (ref "C77") (pin "2") (pinfunction "2_2") (pintype "passive"))
      (node (ref "U1") (pin "P$35") (pinfunction "TDIODE_N_P$35") (pintype "bidirectional"))
      (node (ref "U10") (pin "P$2") (pinfunction "DXN_P$2") (pintype "bidirectional"))
    )
    (net (code "30") (name "ADC_VBG") (class "Default")
      (node (ref "R6") (pin "1") (pinfunction "1_1") (pintype "passive"))
      (node (ref "U1") (pin "P$31") (pinfunction "VBG_P$31") (pintype "output"))
    )
    (net (code "31") (name "ADC_VCMO") (class "Default")
      (node (ref "U1") (pin "P$7") (pinfunction "VCMO_P$7") (pintype "output"))
      (node (ref "U9") (pin "P$1") (pinfunction "+IN_P$1") (pintype "input"))
    )
    (net (code "32") (name "ADC_VCMO_BUFFER") (class "Default")
      (node (ref "U1") (pin "P$22") (pinfunction "VINQ+_P$22") (pintype "input"))
      (node (ref "U1") (pin "P$23") (pinfunction "VINQ-_P$23") (pintype "input"))
      (node (ref "U8") (pin "P$10") (pinfunction "VCM_P$10") (pintype "input"))
      (node (ref "U9") (pin "P$3") (pinfunction "-IN_P$3") (pintype "input"))
      (node (ref "U9") (pin "P$4") (pinfunction "VOUT_P$4") (pintype "output"))
    )
    (net (code "33") (name "ADC_VINI+") (class "Default")
      (node (ref "U1") (pin "P$11") (pinfunction "VINI+_P$11") (pintype "input"))
      (node (ref "U8") (pin "P$8") (pinfunction "VOUT+_P$8") (pintype "output"))
    )
    (net (code "34") (name "ADC_VINI-") (class "Default")
      (node (ref "U1") (pin "P$10") (pinfunction "VINI-_P$10") (pintype "input"))
      (node (ref "U8") (pin "P$13") (pinfunction "VOUT-_P$13") (pintype "output"))
    )
    (net (code "35") (name "ANALOG_PWR_EN") (class "Default")
      (node (ref "R10") (pin "2") (pinfunction "2_2") (pintype "passive"))
      (node (ref "U2") (pin "P$40") (pinfunction "IO_L64N_D9_2_P$40") (pintype "bidirectional"))
      (node (ref "U7") (pin "P$32") (pinfunction "EN_P$32") (pintype "input"))
    )
    (net (code "36") (name "CLK500_N") (class "Default")
      (node (ref "C78") (pin "1") (pinfunction "1_1") (pintype "passive"))
      (node (ref "Y1") (pin "P$5") (pinfunction "CLK-_P$5") (pintype "output"))
    )
    (net (code "37") (name "CLK500_P") (class "Default")
      (node (ref "C79") (pin "1") (pinfunction "1_1") (pintype "passive"))
      (node (ref "Y1") (pin "P$4") (pinfunction "CLK+_P$4") (pintype "output"))
    )
    (net (code "38") (name "DI0_N") (class "Default")
      (node (ref "U1") (pin "P$102") (pinfunction "DI0-_P$102") (pintype "output"))
      (node (ref "U2") (pin "P$102") (pinfunction "IO_L32P_1_P$102") (pintype "bidirectional"))
    )
    (net (code "39") (name "DI0_P") (class "Default")
      (node (ref "U1") (pin "P$103") (pinfunction "DI0+_P$103") (pintype "output"))
      (node (ref "U2") (pin "P$101") (pinfunction "IO_L32N_1_P$101") (pintype "bidirectional"))
    )
    (net (code "40") (name "DI1_N") (class "Default")
      (node (ref "U1") (pin "P$100") (pinfunction "DI1-_P$100") (pintype "output"))
      (node (ref "U2") (pin "P$105") (pinfunction "IO_L1P_1_P$105") (pintype "bidirectional"))
    )
    (net (code "41") (name "DI1_P") (class "Default")
      (node (ref "U1") (pin "P$101") (pinfunction "DI1+_P$101") (pintype "output"))
      (node (ref "U2") (pin "P$104") (pinfunction "IO_L1N_VREF_1_P$104") (pintype "bidirectional"))
    )
    (net (code "42") (name "DI2_N") (class "Default")
      (node (ref "U1") (pin "P$95") (pinfunction "DI2-_P$95") (pintype "output"))
      (node (ref "U2") (pin "P$112") (pinfunction "IO_L66P_SCP1_0_P$112") (pintype "bidirectional"))
    )
    (net (code "43") (name "DI2_P") (class "Default")
      (node (ref "U1") (pin "P$96") (pinfunction "DI2+_P$96") (pintype "output"))
      (node (ref "U2") (pin "P$111") (pinfunction "IO_L66N_SCP0_0_P$111") (pintype "bidirectional"))
    )
    (net (code "44") (name "DI3_N") (class "Default")
      (node (ref "U1") (pin "P$93") (pinfunction "DI3-_P$93") (pintype "output"))
      (node (ref "U2") (pin "P$115") (pinfunction "IO_L65P_SCP3_0_P$115") (pintype "bidirectional"))
    )
    (net (code "45") (name "DI3_P") (class "Default")
      (node (ref "U1") (pin "P$94") (pinfunction "DI3+_P$94") (pintype "output"))
      (node (ref "U2") (pin "P$114") (pinfunction "IO_L65N_SCP2_0_P$114") (pintype "bidirectional"))
    )
    (net (code "46") (name "DI4_N") (class "Default")
      (node (ref "U1") (pin "P$91") (pinfunction "DI4-_P$91") (pintype "output"))
      (node (ref "U2") (pin "P$117") (pinfunction "IO_L64P_SCP5_0_P$117") (pintype "bidirectional"))
    )
    (net (code "47") (name "DI4_P") (class "Default")
      (node (ref "U1") (pin "P$92") (pinfunction "DI4+_P$92") (pintype "output"))
      (node (ref "U2") (pin "P$116") (pinfunction "IO_L64N_SCP4_0_P$116") (pintype "bidirectional"))
    )
    (net (code "48") (name "DI5_N") (class "Default")
      (node (ref "U1") (pin "P$89") (pinfunction "DI5-_P$89") (pintype "output"))
      (node (ref "U2") (pin "P$119") (pinfunction "IO_L63P_SCP7_0_P$119") (pintype "bidirectional"))
    )
    (net (code "49") (name "DI5_P") (class "Default")
      (node (ref "U1") (pin "P$90") (pinfunction "DI5+_P$90") (pintype "output"))
      (node (ref "U2") (pin "P$118") (pinfunction "IO_L63N_SCP6_0_P$118") (pintype "bidirectional"))
    )
    (net (code "50") (name "DI6_N") (class "Default")
      (node (ref "U1") (pin "P$85") (pinfunction "DI6-_P$85") (pintype "output"))
      (node (ref "U2") (pin "P$121") (pinfunction "IO_L62P_0_P$121") (pintype "bidirectional"))
    )
    (net (code "51") (name "DI6_P") (class "Default")
      (node (ref "U1") (pin "P$86") (pinfunction "DI6+_P$86") (pintype "output"))
      (node (ref "U2") (pin "P$120") (pinfunction "IO_L62N_VREF_0_P$120") (pintype "bidirectional"))
    )
    (net (code "52") (name "DI7_N") (class "Default")
      (node (ref "U1") (pin "P$83") (pinfunction "DI7-_P$83") (pintype "output"))
      (node (ref "U2") (pin "P$124") (pinfunction "IO_L37P_GCLK13_0_P$124") (pintype "bidirectional"))
    )
    (net (code "53") (name "DI7_P") (class "Default")
      (node (ref "U1") (pin "P$84") (pinfunction "DI7+_P$84") (pintype "output"))
      (node (ref "U2") (pin "P$123") (pinfunction "IO_L37N_GCLK12_0_P$123") (pintype "bidirectional"))
    )
    (net (code "54") (name "DID0_N") (class "Default")
      (node (ref "U1") (pin "P$124") (pinfunction "DID0-_P$124") (pintype "output"))
      (node (ref "U2") (pin "P$81") (pinfunction "IO_L46P_1_P$81") (pintype "bidirectional"))
    )
    (net (code "55") (name "DID0_P") (class "Default")
      (node (ref "U1") (pin "P$125") (pinfunction "DID0+_P$125") (pintype "output"))
      (node (ref "U2") (pin "P$80") (pinfunction "IO_L46N_1_P$80") (pintype "bidirectional"))
    )
    (net (code "56") (name "DID1_N") (class "Default")
      (node (ref "U1") (pin "P$122") (pinfunction "DID1-_P$122") (pintype "output"))
      (node (ref "U2") (pin "P$83") (pinfunction "IO_L45P_1_P$83") (pintype "bidirectional"))
    )
    (net (code "57") (name "DID1_P") (class "Default")
      (node (ref "U1") (pin "P$123") (pinfunction "DID1+_P$123") (pintype "output"))
      (node (ref "U2") (pin "P$82") (pinfunction "IO_L45N_1_P$82") (pintype "bidirectional"))
    )
    (net (code "58") (name "DID2_N") (class "Default")
      (node (ref "U1") (pin "P$117") (pinfunction "DID2-_P$117") (pintype "output"))
      (node (ref "U2") (pin "P$85") (pinfunction "IO_L43P_GCLK5_1_P$85") (pintype "bidirectional"))
    )
    (net (code "59") (name "DID2_P") (class "Default")
      (node (ref "U1") (pin "P$118") (pinfunction "DID2+_P$118") (pintype "output"))
      (node (ref "U2") (pin "P$84") (pinfunction "IO_L43N_GCLK4_1_P$84") (pintype "bidirectional"))
    )
    (net (code "60") (name "DID3_N") (class "Default")
      (node (ref "U1") (pin "P$115") (pinfunction "DID3-_P$115") (pintype "output"))
      (node (ref "U2") (pin "P$88") (pinfunction "IO_L42P_GCLK7_1_P$88") (pintype "bidirectional"))
    )
    (net (code "61") (name "DID3_P") (class "Default")
      (node (ref "U1") (pin "P$116") (pinfunction "DID3+_P$116") (pintype "output"))
      (node (ref "U2") (pin "P$87") (pinfunction "IO_L42N_GCLK6_TRDY1_1_P$87") (pintype "bidirectional"))
    )
    (net (code "62") (name "DID4_N") (class "Default")
      (node (ref "U1") (pin "P$113") (pinfunction "DID4-_P$113") (pintype "output"))
      (node (ref "U2") (pin "P$93") (pinfunction "IO_L41P_GCLK9_IRDY1_1_P$93") (pintype "bidirectional"))
    )
    (net (code "63") (name "DID4_P") (class "Default")
      (node (ref "U1") (pin "P$114") (pinfunction "DID4+_P$114") (pintype "output"))
      (node (ref "U2") (pin "P$92") (pinfunction "IO_L41N_GCLK8_1_P$92") (pintype "bidirectional"))
    )
    (net (code "64") (name "DID5_N") (class "Default")
      (node (ref "U1") (pin "P$111") (pinfunction "DID5-_P$111") (pintype "output"))
      (node (ref "U2") (pin "P$95") (pinfunction "IO_L40P_GCLK11_1_P$95") (pintype "bidirectional"))
    )
    (net (code "65") (name "DID5_P") (class "Default")
      (node (ref "U1") (pin "P$112") (pinfunction "DID5+_P$112") (pintype "output"))
      (node (ref "U2") (pin "P$94") (pinfunction "IO_L40N_GCLK10_1_P$94") (pintype "bidirectional"))
    )
    (net (code "66") (name "DID6_N") (class "Default")
      (node (ref "U1") (pin "P$106") (pinfunction "DID6-_P$106") (pintype "output"))
      (node (ref "U2") (pin "P$98") (pinfunction "IO_L34P_1_P$98") (pintype "bidirectional"))
    )
    (net (code "67") (name "DID6_P") (class "Default")
      (node (ref "U1") (pin "P$107") (pinfunction "DID6+_P$107") (pintype "output"))
      (node (ref "U2") (pin "P$97") (pinfunction "IO_L34N_1_P$97") (pintype "bidirectional"))
    )
    (net (code "68") (name "DID7_N") (class "Default")
      (node (ref "U1") (pin "P$104") (pinfunction "DID7-_P$104") (pintype "output"))
      (node (ref "U2") (pin "P$100") (pinfunction "IO_L33P_1_P$100") (pintype "bidirectional"))
    )
    (net (code "69") (name "DID7_P") (class "Default")
      (node (ref "U1") (pin "P$105") (pinfunction "DID7+_P$105") (pintype "output"))
      (node (ref "U2") (pin "P$99") (pinfunction "IO_L33N_1_P$99") (pintype "bidirectional"))
    )
    (net (code "70") (name "DQ0_N") (class "Default")
      (node (ref "U1") (pin "P$59") (pinfunction "DQ0-_P$59") (pintype "output"))
      (node (ref "U2") (pin "P$7") (pinfunction "IO_L51N_3_P$7") (pintype "bidirectional"))
    )
    (net (code "71") (name "DQ0_P") (class "Default")
      (node (ref "U1") (pin "P$58") (pinfunction "DQ0+_P$58") (pintype "output"))
      (node (ref "U2") (pin "P$8") (pinfunction "IO_L51P_3_P$8") (pintype "bidirectional"))
    )
    (net (code "72") (name "DQ1_N") (class "Default")
      (node (ref "U1") (pin "P$61") (pinfunction "DQ1-_P$61") (pintype "output"))
      (node (ref "U2") (pin "P$5") (pinfunction "IO_L52N_3_P$5") (pintype "bidirectional"))
    )
    (net (code "73") (name "DQ1_P") (class "Default")
      (node (ref "U1") (pin "P$60") (pinfunction "DQ1+_P$60") (pintype "output"))
      (node (ref "U2") (pin "P$6") (pinfunction "IO_L52P_3_P$6") (pintype "bidirectional"))
    )
    (net (code "74") (name "DQ2_N") (class "Default")
      (node (ref "U1") (pin "P$66") (pinfunction "DQ2-_P$66") (pintype "output"))
      (node (ref "U2") (pin "P$1") (pinfunction "IO_L83N_VREF_3_P$1") (pintype "bidirectional"))
    )
    (net (code "75") (name "DQ2_P") (class "Default")
      (node (ref "U1") (pin "P$65") (pinfunction "DQ2+_P$65") (pintype "output"))
      (node (ref "U2") (pin "P$2") (pinfunction "IO_L83P_3_P$2") (pintype "bidirectional"))
    )
    (net (code "76") (name "DQ3_N") (class "Default")
      (node (ref "U1") (pin "P$67") (pinfunction "DQ3+_P$67") (pintype "output"))
      (node (ref "U2") (pin "P$142") (pinfunction "IO_L2P_0_P$142") (pintype "bidirectional"))
    )
    (net (code "77") (name "DQ3_P") (class "Default")
      (node (ref "U1") (pin "P$68") (pinfunction "DQ3-_P$68") (pintype "output"))
      (node (ref "U2") (pin "P$141") (pinfunction "IO_L2N_0_P$141") (pintype "bidirectional"))
    )
    (net (code "78") (name "DQ4_N") (class "Default")
      (node (ref "U1") (pin "P$69") (pinfunction "DQ4+_P$69") (pintype "output"))
      (node (ref "U2") (pin "P$140") (pinfunction "IO_L3P_0_P$140") (pintype "bidirectional"))
    )
    (net (code "79") (name "DQ4_P") (class "Default")
      (node (ref "U1") (pin "P$70") (pinfunction "DQ4-_P$70") (pintype "output"))
      (node (ref "U2") (pin "P$139") (pinfunction "IO_L3N_0_P$139") (pintype "bidirectional"))
    )
    (net (code "80") (name "DQ5_N") (class "Default")
      (node (ref "U1") (pin "P$71") (pinfunction "DQ5+_P$71") (pintype "output"))
      (node (ref "U2") (pin "P$138") (pinfunction "IO_L4P_0_P$138") (pintype "bidirectional"))
    )
    (net (code "81") (name "DQ5_P") (class "Default")
      (node (ref "U1") (pin "P$72") (pinfunction "DQ5-_P$72") (pintype "output"))
      (node (ref "U2") (pin "P$137") (pinfunction "IO_L4N_0_P$137") (pintype "bidirectional"))
    )
    (net (code "82") (name "DQ6_N") (class "Default")
      (node (ref "U1") (pin "P$75") (pinfunction "DQ6+_P$75") (pintype "output"))
      (node (ref "U2") (pin "P$134") (pinfunction "IO_L34P_GCLK19_0_P$134") (pintype "bidirectional"))
    )
    (net (code "83") (name "DQ6_P") (class "Default")
      (node (ref "U1") (pin "P$76") (pinfunction "DQ6-_P$76") (pintype "output"))
      (node (ref "U2") (pin "P$133") (pinfunction "IO_L34N_GCLK18_0_P$133") (pintype "bidirectional"))
    )
    (net (code "84") (name "DQ7_N") (class "Default")
      (node (ref "U1") (pin "P$77") (pinfunction "DQ7+_P$77") (pintype "output"))
      (node (ref "U2") (pin "P$132") (pinfunction "IO_L35P_GCLK17_0_P$132") (pintype "bidirectional"))
    )
    (net (code "85") (name "DQ7_P") (class "Default")
      (node (ref "U1") (pin "P$78") (pinfunction "DQ7-_P$78") (pintype "output"))
      (node (ref "U2") (pin "P$131") (pinfunction "IO_L35N_GCLK16_0_P$131") (pintype "bidirectional"))
    )
    (net (code "86") (name "DQD0_N") (class "Default")
      (node (ref "U1") (pin "P$37") (pinfunction "DQD0-_P$37") (pintype "output"))
      (node (ref "U2") (pin "P$29") (pinfunction "IO_L36N_3_P$29") (pintype "bidirectional"))
    )
    (net (code "87") (name "DQD0_P") (class "Default")
      (node (ref "U1") (pin "P$36") (pinfunction "DQD0+_P$36") (pintype "output"))
      (node (ref "U2") (pin "P$30") (pinfunction "IO_L36P_3_P$30") (pintype "bidirectional"))
    )
    (net (code "88") (name "DQD1_N") (class "Default")
      (node (ref "U1") (pin "P$39") (pinfunction "DQD1-_P$39") (pintype "output"))
      (node (ref "U2") (pin "P$26") (pinfunction "IO_L37N_3_P$26") (pintype "bidirectional"))
    )
    (net (code "89") (name "DQD1_P") (class "Default")
      (node (ref "U1") (pin "P$38") (pinfunction "DQD1+_P$38") (pintype "output"))
      (node (ref "U2") (pin "P$27") (pinfunction "IO_L37P_3_P$27") (pintype "bidirectional"))
    )
    (net (code "90") (name "DQD2_N") (class "Default")
      (node (ref "U1") (pin "P$44") (pinfunction "DQD2-_P$44") (pintype "output"))
      (node (ref "U2") (pin "P$23") (pinfunction "IO_L41N_GCLK26_3_P$23") (pintype "bidirectional"))
    )
    (net (code "91") (name "DQD2_P") (class "Default")
      (node (ref "U1") (pin "P$43") (pinfunction "DQD2+_P$43") (pintype "output"))
      (node (ref "U2") (pin "P$24") (pinfunction "IO_L41P_GCLK27_3_P$24") (pintype "bidirectional"))
    )
    (net (code "92") (name "DQD3_N") (class "Default")
      (node (ref "U1") (pin "P$46") (pinfunction "DQD3-_P$46") (pintype "output"))
      (node (ref "U2") (pin "P$21") (pinfunction "IO_L42N_GCLK24_3_P$21") (pintype "bidirectional"))
    )
    (net (code "93") (name "DQD3_P") (class "Default")
      (node (ref "U1") (pin "P$45") (pinfunction "DQD3+_P$45") (pintype "output"))
      (node (ref "U2") (pin "P$22") (pinfunction "IO_L42P_GCLK25_TRDY2_3_P$22") (pintype "bidirectional"))
    )
    (net (code "94") (name "DQD4_N") (class "Default")
      (node (ref "U1") (pin "P$48") (pinfunction "DQD4-_P$48") (pintype "output"))
      (node (ref "U2") (pin "P$16") (pinfunction "IO_L43N_GCLK22_IRDY2_3_P$16") (pintype "bidirectional"))
    )
    (net (code "95") (name "DQD4_P") (class "Default")
      (node (ref "U1") (pin "P$47") (pinfunction "DQD4+_P$47") (pintype "output"))
      (node (ref "U2") (pin "P$17") (pinfunction "IO_L43P_GCLK23_3_P$17") (pintype "bidirectional"))
    )
    (net (code "96") (name "DQD5_N") (class "Default")
      (node (ref "U1") (pin "P$50") (pinfunction "DQD5-_P$50") (pintype "output"))
      (node (ref "U2") (pin "P$14") (pinfunction "IO_L44N_GCLK20_3_P$14") (pintype "bidirectional"))
    )
    (net (code "97") (name "DQD5_P") (class "Default")
      (node (ref "U1") (pin "P$49") (pinfunction "DQD5+_P$49") (pintype "output"))
      (node (ref "U2") (pin "P$15") (pinfunction "IO_L44P_GCLK21_3_P$15") (pintype "bidirectional"))
    )
    (net (code "98") (name "DQD6_N") (class "Default")
      (node (ref "U1") (pin "P$55") (pinfunction "DQD6-_P$55") (pintype "output"))
      (node (ref "U2") (pin "P$11") (pinfunction "IO_L49N_3_P$11") (pintype "bidirectional"))
    )
    (net (code "99") (name "DQD6_P") (class "Default")
      (node (ref "U1") (pin "P$54") (pinfunction "DQD6+_P$54") (pintype "output"))
      (node (ref "U2") (pin "P$12") (pinfunction "IO_L49P_3_P$12") (pintype "bidirectional"))
    )
    (net (code "100") (name "DQD7_N") (class "Default")
      (node (ref "U1") (pin "P$57") (pinfunction "DQD7-_P$57") (pintype "output"))
      (node (ref "U2") (pin "P$9") (pinfunction "IO_L50N_3_P$9") (pintype "bidirectional"))
    )
    (net (code "101") (name "DQD7_P") (class "Default")
      (node (ref "U1") (pin "P$56") (pinfunction "DQD7+_P$56") (pintype "output"))
      (node (ref "U2") (pin "P$10") (pinfunction "IO_L50P_3_P$10") (pintype "bidirectional"))
    )
    (net (code "102") (name "FPGA_CCLK") (class "Default")
      (node (ref "R53") (pin "1") (pinfunction "1_1") (pintype "passive"))
      (node (ref "R54") (pin "2") (pinfunction "2_2") (pintype "passive"))
      (node (ref "U13") (pin "P$3") (pinfunction "CLK_P$3") (pintype "input"))
      (node (ref "U2") (pin "P$70") (pinfunction "IO_L1P_CCLK_2_P$70") (pintype "bidirectional"))
    )
    (net (code "103") (name "FPGA_CLK1") (class "Default")
      (node (ref "U2") (pin "P$55") (pinfunction "IO_L30N_GCLK0_USERCCLK_2_P$55") (pintype "bidirectional"))
      (node (ref "Y2") (pin "P$1") (pinfunction "OUT_P$1") (pintype "output"))
    )
    (net (code "104") (name "FPGA_CLK2") (class "Default")
      (node (ref "U2") (pin "P$56") (pinfunction "IO_L30P_GCLK1_D13_2_P$56") (pintype "bidirectional"))
      (node (ref "Y3") (pin "P$3") (pinfunction "OUTPUT_P$3") (pintype "output"))
    )
    (net (code "105") (name "FPGA_CSO") (class "Default")
      (node (ref "U2") (pin "P$38") (pinfunction "IO_L65N_CSO_B_2_P$38") (pintype "bidirectional"))
    )
    (net (code "106") (name "FPGA_CTS") (class "Default")
      (node (ref "U14") (pin "4") (pinfunction "~{CTS}_4") (pintype "input"))
      (node (ref "U2") (pin "P$58") (pinfunction "IO_L14P_D11_2_P$58") (pintype "bidirectional"))
    )
    (net (code "107") (name "FPGA_DIN") (class "Default")
      (node (ref "U13") (pin "P$1") (pinfunction "DO_P$1") (pintype "bidirectional"))
      (node (ref "U2") (pin "P$65") (pinfunction "IO_L3P_D0_DIN_MISO_MISO1_2_P$65") (pintype "bidirectional"))
    )
    (net (code "108") (name "FPGA_DONE") (class "Default")
      (node (ref "R55") (pin "1") (pinfunction "1_1") (pintype "passive"))
      (node (ref "U13") (pin "P$10") (pinfunction "~{CE}_P$10") (pintype "bidirectional"))
      (node (ref "U2") (pin "P$71") (pinfunction "DONE_2_P$71") (pintype "bidirectional"))
    )
    (net (code "109") (name "FPGA_DOUT") (class "Default")
      (node (ref "U2") (pin "P$74") (pinfunction "IO_L74N_DOUT_BUSY_1_P$74") (pintype "bidirectional"))
    )
    (net (code "110") (name "FPGA_GPIO1") (class "Default")
      (node (ref "D4") (pin "CATHODE") (pinfunction "CATHODE_CATHODE") (pintype "bidirectional"))
      (node (ref "U2") (pin "P$47") (pinfunction "IO_L48N_RDWR_B_VREF_2_P$47") (pintype "bidirectional"))
      (node (ref "X3") (pin "P$4") (pinfunction "P$4_P$4") (pintype "bidirectional"))
    )
    (net (code "111") (name "FPGA_GPIO2") (class "Default")
      (node (ref "U2") (pin "P$48") (pinfunction "IO_L48P_D7_2_P$48") (pintype "bidirectional"))
      (node (ref "X3") (pin "P$2") (pinfunction "P$2_P$2") (pintype "bidirectional"))
    )
    (net (code "112") (name "FPGA_GPIO3") (class "Default")
      (node (ref "D3") (pin "CATHODE") (pinfunction "CATHODE_CATHODE") (pintype "bidirectional"))
      (node (ref "U2") (pin "P$57") (pinfunction "IO_L14N_D12_2_P$57") (pintype "bidirectional"))
      (node (ref "X3") (pin "P$1") (pinfunction "P$1_P$1") (pintype "bidirectional"))
    )
    (net (code "113") (name "FPGA_GPIO4") (class "Default")
      (node (ref "D2") (pin "CATHODE") (pinfunction "CATHODE_CATHODE") (pintype "bidirectional"))
      (node (ref "U2") (pin "P$62") (pinfunction "IO_L12P_D1_MISO2_2_P$62") (pintype "bidirectional"))
      (node (ref "X3") (pin "P$3") (pinfunction "P$3_P$3") (pintype "bidirectional"))
    )
    (net (code "114") (name "FPGA_INITB") (class "Default")
      (node (ref "R59") (pin "1") (pinfunction "1_1") (pintype "passive"))
      (node (ref "U13") (pin "P$8") (pinfunction "OE/~{RST}_P$8") (pintype "bidirectional"))
      (node (ref "U2") (pin "P$39") (pinfunction "IO_L65P_INIT_B_2_P$39") (pintype "bidirectional"))
    )
    (net (code "115") (name "FPGA_MOSI") (class "Default")
      (node (ref "U2") (pin "P$66") (pinfunction "IO_L2N_CMPMOSI_2_P$66") (pintype "bidirectional"))
    )
    (net (code "116") (name "FPGA_PROGRAMB") (class "Default")
      (node (ref "R58") (pin "2") (pinfunction "2_2") (pintype "passive"))
      (node (ref "R9") (pin "1") (pinfunction "1_1") (pintype "passive"))
      (node (ref "U2") (pin "P$37") (pinfunction "PROGRAM_B_2_P$37") (pintype "bidirectional"))
    )
    (net (code "117") (name "FPGA_RXD") (class "Default")
      (node (ref "R56") (pin "2") (pinfunction "2_2") (pintype "passive"))
      (node (ref "U2") (pin "P$67") (pinfunction "IO_L2P_CMPCLK_2_P$67") (pintype "bidirectional"))
    )
    (net (code "118") (name "FPGA_SCL") (class "Default")
      (node (ref "R41") (pin "1") (pinfunction "1_1") (pintype "passive"))
      (node (ref "U10") (pin "P$7") (pinfunction "SCL_P$7") (pintype "input"))
      (node (ref "U11") (pin "P$5") (pinfunction "SCL_P$5") (pintype "input"))
      (node (ref "U2") (pin "P$43") (pinfunction "IO_L62N_D6_2_P$43") (pintype "bidirectional"))
    )
    (net (code "119") (name "FPGA_SDA") (class "Default")
      (node (ref "R44") (pin "1") (pinfunction "1_1") (pintype "passive"))
      (node (ref "U10") (pin "P$6") (pinfunction "SDA_P$6") (pintype "bidirectional"))
      (node (ref "U11") (pin "P$4") (pinfunction "SDA_P$4") (pintype "bidirectional"))
      (node (ref "U2") (pin "P$44") (pinfunction "IO_L62P_D5_2_P$44") (pintype "bidirectional"))
    )
    (net (code "120") (name "FPGA_TCK") (class "Default")
      (node (ref "U13") (pin "P$6") (pinfunction "TCK_P$6") (pintype "bidirectional"))
      (node (ref "U2") (pin "P$109") (pinfunction "TCK_P$109") (pintype "bidirectional"))
      (node (ref "X4") (pin "6") (pinfunction "6_6") (pintype "passive"))
    )
    (net (code "121") (name "FPGA_TDI") (class "Default")
      (node (ref "U2") (pin "P$110") (pinfunction "TDI_P$110") (pintype "bidirectional"))
      (node (ref "X4") (pin "10") (pinfunction "10_10") (pintype "passive"))
    )
    (net (code "122") (name "FPGA_TDO") (class "Default")
      (node (ref "U13") (pin "P$4") (pinfunction "TDI_P$4") (pintype "bidirectional"))
      (node (ref "U2") (pin "P$106") (pinfunction "TDO_P$106") (pintype "bidirectional"))
    )
    (net (code "123") (name "FPGA_TMS") (class "Default")
      (node (ref "U13") (pin "P$5") (pinfunction "TMS_P$5") (pintype "bidirectional"))
      (node (ref "U2") (pin "P$107") (pinfunction "TMS_P$107") (pintype "bidirectional"))
      (node (ref "X4") (pin "4") (pinfunction "4_4") (pintype "passive"))
    )
    (net (code "124") (name "FPGA_TRIG_N") (class "Default")
      (node (ref "R47") (pin "2") (pinfunction "2_2") (pintype "passive"))
      (node (ref "R50") (pin "2") (pinfunction "2_2") (pintype "passive"))
      (node (ref "U12") (pin "5") (pinfunction "~{QA}_5") (pintype "output"))
      (node (ref "U2") (pin "P$50") (pinfunction "IO_L31N_GCLK30_D15_2_P$50") (pintype "bidirectional"))
    )
    (net (code "125") (name "FPGA_TRIG_P") (class "Default")
      (node (ref "R43") (pin "2") (pinfunction "2_2") (pintype "passive"))
      (node (ref "R52") (pin "2") (pinfunction "2_2") (pintype "passive"))
      (node (ref "U12") (pin "6") (pinfunction "QA_6") (pintype "output"))
      (node (ref "U2") (pin "P$51") (pinfunction "IO_L31P_GCLK31_D14_2_P$51") (pintype "bidirectional"))
    )
    (net (code "126") (name "FPGA_TXD") (class "Default")
      (node (ref "R57") (pin "2") (pinfunction "2_2") (pintype "passive"))
      (node (ref "U2") (pin "P$64") (pinfunction "IO_L3N_MOSI_CSI_B_MISO0_2_P$64") (pintype "bidirectional"))
    )
    (net (code "127") (name "FTDI_RXD") (class "Default")
      (node (ref "R57") (pin "1") (pinfunction "1_1") (pintype "passive"))
      (node (ref "U14") (pin "2") (pinfunction "RXD_2") (pintype "input"))
    )
    (net (code "128") (name "FTDI_TXD") (class "Default")
      (node (ref "R56") (pin "1") (pinfunction "1_1") (pintype "passive"))
      (node (ref "U14") (pin "15") (pinfunction "TXD_15") (pintype "output"))
    )
    (net (code "129") (name "GND") (class "Default")
      (node (ref "C1") (pin "2") (pinfunction "2_2") (pintype "passive"))
      (node (ref "C100") (pin "1") (pinfunction "1_1") (pintype "passive"))
      (node (ref "C101") (pin "P$1") (pinfunction "1_P$1") (pintype "passive"))
      (node (ref "C102") (pin "P$2") (pinfunction "2_P$2") (pintype "passive"))
      (node (ref "C103") (pin "P$1") (pinfunction "1_P$1") (pintype "passive"))
      (node (ref "C104") (pin "P$2") (pinfunction "2_P$2") (pintype "passive"))
      (node (ref "C105") (pin "P$1") (pinfunction "1_P$1") (pintype "passive"))
      (node (ref "C12") (pin "2") (pinfunction "2_2") (pintype "passive"))
      (node (ref "C13") (pin "2") (pinfunction "2_2") (pintype "passive"))
      (node (ref "C15") (pin "2") (pinfunction "2_2") (pintype "passive"))
      (node (ref "C16") (pin "2") (pinfunction "2_2") (pintype "passive"))
      (node (ref "C17") (pin "2") (pinfunction "2_2") (pintype "passive"))
      (node (ref "C18") (pin "2") (pinfunction "2_2") (pintype "passive"))
      (node (ref "C19") (pin "2") (pinfunction "2_2") (pintype "passive"))
      (node (ref "C2") (pin "2") (pinfunction "2_2") (pintype "passive"))
      (node (ref "C20") (pin "2") (pinfunction "2_2") (pintype "passive"))
      (node (ref "C21") (pin "2") (pinfunction "2_2") (pintype "passive"))
      (node (ref "C22") (pin "2") (pinfunction "2_2") (pintype "passive"))
      (node (ref "C23") (pin "2") (pinfunction "2_2") (pintype "passive"))
      (node (ref "C24") (pin "2") (pinfunction "2_2") (pintype "passive"))
      (node (ref "C25") (pin "2") (pinfunction "2_2") (pintype "passive"))
      (node (ref "C26") (pin "2") (pinfunction "2_2") (pintype "passive"))
      (node (ref "C3") (pin "2") (pinfunction "2_2") (pintype "passive"))
      (node (ref "C30") (pin "2") (pinfunction "2_2") (pintype "passive"))
      (node (ref "C31") (pin "2") (pinfunction "2_2") (pintype "passive"))
      (node (ref "C32") (pin "2") (pinfunction "2_2") (pintype "passive"))
      (node (ref "C33") (pin "P$2") (pinfunction "2_P$2") (pintype "passive"))
      (node (ref "C34") (pin "P$2") (pinfunction "2_P$2") (pintype "passive"))
      (node (ref "C35") (pin "P$2") (pinfunction "2_P$2") (pintype "passive"))
      (node (ref "C36") (pin "P$2") (pinfunction "2_P$2") (pintype "passive"))
      (node (ref "C37") (pin "P$2") (pinfunction "2_P$2") (pintype "passive"))
      (node (ref "C38") (pin "P$2") (pinfunction "2_P$2") (pintype "passive"))
      (node (ref "C39") (pin "2") (pinfunction "2_2") (pintype "passive"))
      (node (ref "C4") (pin "2") (pinfunction "2_2") (pintype "passive"))
      (node (ref "C40") (pin "2") (pinfunction "2_2") (pintype "passive"))
      (node (ref "C41") (pin "P$2") (pinfunction "2_P$2") (pintype "passive"))
      (node (ref "C42") (pin "P$2") (pinfunction "2_P$2") (pintype "passive"))
      (node (ref "C43") (pin "P$2") (pinfunction "2_P$2") (pintype "passive"))
      (node (ref "C44") (pin "P$2") (pinfunction "2_P$2") (pintype "passive"))
      (node (ref "C45") (pin "P$2") (pinfunction "2_P$2") (pintype "passive"))
      (node (ref "C46") (pin "P$2") (pinfunction "2_P$2") (pintype "passive"))
      (node (ref "C47") (pin "P$1") (pinfunction "1_P$1") (pintype "passive"))
      (node (ref "C48") (pin "P$2") (pinfunction "2_P$2") (pintype "passive"))
      (node (ref "C49") (pin "P$1") (pinfunction "1_P$1") (pintype "passive"))
      (node (ref "C5") (pin "2") (pinfunction "2_2") (pintype "passive"))
      (node (ref "C50") (pin "P$2") (pinfunction "2_P$2") (pintype "passive"))
      (node (ref "C51") (pin "P$2") (pinfunction "2_P$2") (pintype "passive"))
      (node (ref "C52") (pin "P$2") (pinfunction "2_P$2") (pintype "passive"))
      (node (ref "C53") (pin "P$2") (pinfunction "2_P$2") (pintype "passive"))
      (node (ref "C54") (pin "P$2") (pinfunction "2_P$2") (pintype "passive"))
      (node (ref "C55") (pin "P$2") (pinfunction "2_P$2") (pintype "passive"))
      (node (ref "C56") (pin "P$2") (pinfunction "2_P$2") (pintype "passive"))
      (node (ref "C57") (pin "P$2") (pinfunction "2_P$2") (pintype "passive"))
      (node (ref "C58") (pin "P$2") (pinfunction "2_P$2") (pintype "passive"))
      (node (ref "C59") (pin "P$2") (pinfunction "2_P$2") (pintype "passive"))
      (node (ref "C6") (pin "P$2") (pinfunction "NEG_P$2") (pintype "passive"))
      (node (ref "C60") (pin "P$2") (pinfunction "2_P$2") (pintype "passive"))
      (node (ref "C61") (pin "P$2") (pinfunction "2_P$2") (pintype "passive"))
      (node (ref "C62") (pin "P$2") (pinfunction "2_P$2") (pintype "passive"))
      (node (ref "C63") (pin "P$2") (pinfunction "2_P$2") (pintype "passive"))
      (node (ref "C64") (pin "P$1") (pinfunction "1_P$1") (pintype "passive"))
      (node (ref "C65") (pin "P$2") (pinfunction "2_P$2") (pintype "passive"))
      (node (ref "C66") (pin "P$2") (pinfunction "2_P$2") (pintype "passive"))
      (node (ref "C67") (pin "P$2") (pinfunction "2_P$2") (pintype "passive"))
      (node (ref "C68") (pin "P$2") (pinfunction "2_P$2") (pintype "passive"))
      (node (ref "C69") (pin "P$2") (pinfunction "2_P$2") (pintype "passive"))
      (node (ref "C7") (pin "P$2") (pinfunction "2_P$2") (pintype "passive"))
      (node (ref "C70") (pin "P$2") (pinfunction "2_P$2") (pintype "passive"))
      (node (ref "C71") (pin "P$2") (pinfunction "2_P$2") (pintype "passive"))
      (node (ref "C72") (pin "P$2") (pinfunction "2_P$2") (pintype "passive"))
      (node (ref "C73") (pin "P$1") (pinfunction "1_P$1") (pintype "passive"))
      (node (ref "C74") (pin "P$2") (pinfunction "2_P$2") (pintype "passive"))
      (node (ref "C75") (pin "P$2") (pinfunction "2_P$2") (pintype "passive"))
      (node (ref "C76") (pin "P$2") (pinfunction "2_P$2") (pintype "passive"))
      (node (ref "C8") (pin "2") (pinfunction "2_2") (pintype "passive"))
      (node (ref "C80") (pin "P$2") (pinfunction "2_P$2") (pintype "passive"))
      (node (ref "C81") (pin "P$2") (pinfunction "2_P$2") (pintype "passive"))
      (node (ref "C82") (pin "P$2") (pinfunction "2_P$2") (pintype "passive"))
      (node (ref "C83") (pin "2") (pinfunction "2_2") (pintype "passive"))
      (node (ref "C84") (pin "P$2") (pinfunction "2_P$2") (pintype "passive"))
      (node (ref "C85") (pin "2") (pinfunction "2_2") (pintype "passive"))
      (node (ref "C86") (pin "P$2") (pinfunction "2_P$2") (pintype "passive"))
      (node (ref "C87") (pin "P$2") (pinfunction "2_P$2") (pintype "passive"))
      (node (ref "C88") (pin "2") (pinfunction "2_2") (pintype "passive"))
      (node (ref "C89") (pin "P$2") (pinfunction "2_P$2") (pintype "passive"))
      (node (ref "C9") (pin "2") (pinfunction "2_2") (pintype "passive"))
      (node (ref "C90") (pin "P$2") (pinfunction "2_P$2") (pintype "passive"))
      (node (ref "C91") (pin "P$2") (pinfunction "2_P$2") (pintype "passive"))
      (node (ref "C92") (pin "P$2") (pinfunction "2_P$2") (pintype "passive"))
      (node (ref "C93") (pin "2") (pinfunction "2_2") (pintype "passive"))
      (node (ref "C94") (pin "2") (pinfunction "2_2") (pintype "passive"))
      (node (ref "C95") (pin "2") (pinfunction "2_2") (pintype "passive"))
      (node (ref "C96") (pin "P$2") (pinfunction "2_P$2") (pintype "passive"))
      (node (ref "C97") (pin "2") (pinfunction "2_2") (pintype "passive"))
      (node (ref "C98") (pin "2") (pinfunction "2_2") (pintype "passive"))
      (node (ref "C99") (pin "1") (pinfunction "1_1") (pintype "passive"))
      (node (ref "D1") (pin "CATHODE") (pinfunction "CATHODE_CATHODE") (pintype "bidirectional"))
      (node (ref "J2") (pin "GND") (pinfunction "GND_GND") (pintype "power_in"))
      (node (ref "L1") (pin "P$4") (pinfunction "P$4_P$4") (pintype "bidirectional"))
      (node (ref "PAD1") (pin "1") (pinfunction "P_1") (pintype "passive"))
      (node (ref "PAD2") (pin "1") (pinfunction "P_1") (pintype "passive"))
      (node (ref "PAD3") (pin "1") (pinfunction "P_1") (pintype "passive"))
      (node (ref "PAD4") (pin "1") (pinfunction "P_1") (pintype "passive"))
      (node (ref "R10") (pin "1") (pinfunction "1_1") (pintype "passive"))
      (node (ref "R12") (pin "2") (pinfunction "2_2") (pintype "passive"))
      (node (ref "R14") (pin "1") (pinfunction "1_1") (pintype "passive"))
      (node (ref "R15") (pin "1") (pinfunction "1_1") (pintype "passive"))
      (node (ref "R18") (pin "1") (pinfunction "1_1") (pintype "passive"))
      (node (ref "R19") (pin "1") (pinfunction "1_1") (pintype "passive"))
      (node (ref "R2") (pin "1") (pinfunction "1_1") (pintype "passive"))
      (node (ref "R22") (pin "1") (pinfunction "1_1") (pintype "passive"))
      (node (ref "R24") (pin "1") (pinfunction "1_1") (pintype "passive"))
      (node (ref "R28") (pin "1") (pinfunction "1_1") (pintype "passive"))
      (node (ref "R30") (pin "1") (pinfunction "1_1") (pintype "passive"))
      (node (ref "R31") (pin "1") (pinfunction "1_1") (pintype "passive"))
      (node (ref "R34") (pin "1") (pinfunction "1_1") (pintype "passive"))
      (node (ref "R36") (pin "1") (pinfunction "1_1") (pintype "passive"))
      (node (ref "R37") (pin "1") (pinfunction "1_1") (pintype "passive"))
      (node (ref "R39") (pin "1") (pinfunction "1_1") (pintype "passive"))
      (node (ref "R4") (pin "1") (pinfunction "1_1") (pintype "passive"))
      (node (ref "R40") (pin "1") (pinfunction "1_1") (pintype "passive"))
      (node (ref "R51") (pin "1") (pinfunction "1_1") (pintype "passive"))
      (node (ref "R54") (pin "1") (pinfunction "1_1") (pintype "passive"))
      (node (ref "R7") (pin "1") (pinfunction "1_1") (pintype "passive"))
      (node (ref "S1") (pin "P$1") (pinfunction "P$1_P$1") (pintype "bidirectional"))
      (node (ref "U1") (pin "P$1") (pinfunction "GND_P$1") (pintype "passive"))
      (node (ref "U1") (pin "P$108") (pinfunction "DR_GND_P$108") (pintype "passive"))
      (node (ref "U1") (pin "P$119") (pinfunction "DR_GND_P$119") (pintype "passive"))
      (node (ref "U1") (pin "P$12") (pinfunction "GND_P$12") (pintype "passive"))
      (node (ref "U1") (pin "P$129") (pinfunction "GND_P$129") (pintype "power_in"))
      (node (ref "U1") (pin "P$130") (pinfunction "GND_P$130") (pintype "power_in"))
      (node (ref "U1") (pin "P$131") (pinfunction "GND_P$131") (pintype "power_in"))
      (node (ref "U1") (pin "P$132") (pinfunction "GND_P$132") (pintype "power_in"))
      (node (ref "U1") (pin "P$133") (pinfunction "GND_P$133") (pintype "power_in"))
      (node (ref "U1") (pin "P$134") (pinfunction "GND_P$134") (pintype "power_in"))
      (node (ref "U1") (pin "P$135") (pinfunction "GND_P$135") (pintype "power_in"))
      (node (ref "U1") (pin "P$136") (pinfunction "GND_P$136") (pintype "power_in"))
      (node (ref "U1") (pin "P$137") (pinfunction "GND_P$137") (pintype "power_in"))
      (node (ref "U1") (pin "P$138") (pinfunction "GND_P$138") (pintype "power_in"))
      (node (ref "U1") (pin "P$139") (pinfunction "GND_P$139") (pintype "power_in"))
      (node (ref "U1") (pin "P$140") (pinfunction "GND_P$140") (pintype "power_in"))
      (node (ref "U1") (pin "P$141") (pinfunction "GND_P$141") (pintype "power_in"))
      (node (ref "U1") (pin "P$142") (pinfunction "GND_P$142") (pintype "power_in"))
      (node (ref "U1") (pin "P$143") (pinfunction "GND_P$143") (pintype "power_in"))
      (node (ref "U1") (pin "P$144") (pinfunction "GND_P$144") (pintype "power_in"))
      (node (ref "U1") (pin "P$21") (pinfunction "GND_P$21") (pintype "passive"))
      (node (ref "U1") (pin "P$24") (pinfunction "GND_P$24") (pintype "passive"))
      (node (ref "U1") (pin "P$27") (pinfunction "GND_P$27") (pintype "passive"))
      (node (ref "U1") (pin "P$41") (pinfunction "GND_P$41") (pintype "passive"))
      (node (ref "U1") (pin "P$42") (pinfunction "DR_GND_P$42") (pintype "passive"))
      (node (ref "U1") (pin "P$53") (pinfunction "DR_GND_P$53") (pintype "passive"))
      (node (ref "U1") (pin "P$6") (pinfunction "GND_P$6") (pintype "passive"))
      (node (ref "U1") (pin "P$64") (pinfunction "DR_GND_P$64") (pintype "passive"))
      (node (ref "U1") (pin "P$74") (pinfunction "DR_GND_P$74") (pintype "passive"))
      (node (ref "U1") (pin "P$87") (pinfunction "DR_GND_P$87") (pintype "passive"))
      (node (ref "U1") (pin "P$9") (pinfunction "GND_P$9") (pintype "passive"))
      (node (ref "U1") (pin "P$97") (pinfunction "DR_GND_P$97") (pintype "passive"))
      (node (ref "U10") (pin "P$3") (pinfunction "A1_P$3") (pintype "input"))
      (node (ref "U10") (pin "P$4") (pinfunction "A0_P$4") (pintype "input"))
      (node (ref "U10") (pin "P$5") (pinfunction "GND_P$5") (pintype "power_in"))
      (node (ref "U11") (pin "P$3") (pinfunction "GND_P$3") (pintype "power_in"))
      (node (ref "U11") (pin "P$6") (pinfunction "ADR0_P$6") (pintype "input"))
      (node (ref "U12") (pin "8") (pinfunction "GND_8") (pintype "power_in"))
      (node (ref "U13") (pin "P$11") (pinfunction "GND_P$11") (pintype "power_in"))
      (node (ref "U14") (pin "13") (pinfunction "GND_13") (pintype "power_in"))
      (node (ref "U14") (pin "3") (pinfunction "GND_3") (pintype "power_in"))
      (node (ref "U14") (pin "TAB") (pinfunction "PAD_TAB") (pintype "power_in"))
      (node (ref "U2") (pin "P$108") (pinfunction "GND_P$108") (pintype "power_in"))
      (node (ref "U2") (pin "P$113") (pinfunction "GND_P$113") (pintype "power_in"))
      (node (ref "U2") (pin "P$13") (pinfunction "GND_P$13") (pintype "power_in"))
      (node (ref "U2") (pin "P$130") (pinfunction "GND_P$130") (pintype "power_in"))
      (node (ref "U2") (pin "P$136") (pinfunction "GND_P$136") (pintype "power_in"))
      (node (ref "U2") (pin "P$25") (pinfunction "GND_P$25") (pintype "power_in"))
      (node (ref "U2") (pin "P$3") (pinfunction "GND_P$3") (pintype "power_in"))
      (node (ref "U2") (pin "P$49") (pinfunction "GND_P$49") (pintype "power_in"))
      (node (ref "U2") (pin "P$54") (pinfunction "GND_P$54") (pintype "power_in"))
      (node (ref "U2") (pin "P$60") (pinfunction "IO_L13P_M1_2_P$60") (pintype "bidirectional"))
      (node (ref "U2") (pin "P$68") (pinfunction "GND_P$68") (pintype "power_in"))
      (node (ref "U2") (pin "P$73") (pinfunction "SUSPEND_P$73") (pintype "bidirectional"))
      (node (ref "U2") (pin "P$77") (pinfunction "GND_P$77") (pintype "power_in"))
      (node (ref "U2") (pin "P$91") (pinfunction "GND_P$91") (pintype "power_in"))
      (node (ref "U2") (pin "P$96") (pinfunction "GND_P$96") (pintype "power_in"))
      (node (ref "U3") (pin "P$11") (pinfunction "PAD_P$11") (pintype "power_in"))
      (node (ref "U3") (pin "P$6") (pinfunction "GND_P$6") (pintype "power_in"))
      (node (ref "U4") (pin "2") (pinfunction "GND_2") (pintype "power_in"))
      (node (ref "U4") (pin "4") (pinfunction "GND_4") (pintype "power_in"))
      (node (ref "U5") (pin "2") (pinfunction "GND_2") (pintype "power_in"))
      (node (ref "U5") (pin "4") (pinfunction "GND_4") (pintype "power_in"))
      (node (ref "U6") (pin "3") (pinfunction "GND_3") (pintype "power_in"))
      (node (ref "U6") (pin "6") (pinfunction "GND_6") (pintype "power_in"))
      (node (ref "U7") (pin "P$16") (pinfunction "SYNC_P$16") (pintype "input"))
      (node (ref "U7") (pin "P$18") (pinfunction "EN_P$18") (pintype "input"))
      (node (ref "U7") (pin "P$37") (pinfunction "EN_P$37") (pintype "input"))
      (node (ref "U7") (pin "P$39") (pinfunction "GND_P$39") (pintype "power_in"))
      (node (ref "U8") (pin "P$1") (pinfunction "GND_P$1") (pintype "power_in"))
      (node (ref "U8") (pin "P$14") (pinfunction "GND_P$14") (pintype "power_in"))
      (node (ref "U8") (pin "P$15") (pinfunction "GND_P$15") (pintype "power_in"))
      (node (ref "U8") (pin "P$17") (pinfunction "XPAD_P$17") (pintype "power_in"))
      (node (ref "U8") (pin "P$2") (pinfunction "GND_P$2") (pintype "power_in"))
      (node (ref "U8") (pin "P$3") (pinfunction "GND_P$3") (pintype "power_in"))
      (node (ref "U8") (pin "P$4") (pinfunction "GND_P$4") (pintype "power_in"))
      (node (ref "U8") (pin "P$6") (pinfunction "GND_P$6") (pintype "power_in"))
      (node (ref "U8") (pin "P$7") (pinfunction "GND_P$7") (pintype "power_in"))
      (node (ref "U9") (pin "P$2") (pinfunction "V-_P$2") (pintype "power_in"))
      (node (ref "X1") (pin "G@1") (pinfunction "2_G@1") (pintype "passive"))
      (node (ref "X1") (pin "G@2") (pinfunction "2_G@2") (pintype "passive"))
      (node (ref "X1") (pin "G@3") (pinfunction "2_G@3") (pintype "passive"))
      (node (ref "X1") (pin "G@4") (pinfunction "2_G@4") (pintype "passive"))
      (node (ref "X2") (pin "G@1") (pinfunction "2_G@1") (pintype "passive"))
      (node (ref "X2") (pin "G@2") (pinfunction "2_G@2") (pintype "passive"))
      (node (ref "X2") (pin "G@3") (pinfunction "2_G@3") (pintype "passive"))
      (node (ref "X2") (pin "G@4") (pinfunction "2_G@4") (pintype "passive"))
      (node (ref "X3") (pin "P$8") (pinfunction "P$8_P$8") (pintype "bidirectional"))
      (node (ref "X4") (pin "1") (pinfunction "1_1") (pintype "passive"))
      (node (ref "X4") (pin "11") (pinfunction "11_11") (pintype "passive"))
      (node (ref "X4") (pin "13") (pinfunction "13_13") (pintype "passive"))
      (node (ref "X4") (pin "3") (pinfunction "3_3") (pintype "passive"))
      (node (ref "X4") (pin "5") (pinfunction "5_5") (pintype "passive"))
      (node (ref "X4") (pin "7") (pinfunction "7_7") (pintype "passive"))
      (node (ref "X4") (pin "9") (pinfunction "9_9") (pintype "passive"))
      (node (ref "Y1") (pin "P$3") (pinfunction "GND_P$3") (pintype "power_in"))
      (node (ref "Y2") (pin "P$4") (pinfunction "GND_P$4") (pintype "power_in"))
      (node (ref "Y2") (pin "P$5") (pinfunction "GND_P$5") (pintype "power_in"))
      (node (ref "Y3") (pin "P$2") (pinfunction "GND_P$2") (pintype "power_in"))
    )
    (net (code "130") (name "Net-(C6-POS)") (class "Default")
      (node (ref "C6") (pin "P$1") (pinfunction "POS_P$1") (pintype "passive"))
      (node (ref "L1") (pin "P$3") (pinfunction "P$3_P$3") (pintype "bidirectional"))
      (node (ref "L2") (pin "P$1") (pinfunction "P$1_P$1") (pintype "bidirectional"))
    )
    (net (code "131") (name "Net-(C86-1)") (class "Default")
      (node (ref "C85") (pin "1") (pinfunction "1_1") (pintype "passive"))
      (node (ref "C86") (pin "P$1") (pinfunction "1_P$1") (pintype "passive"))
      (node (ref "C87") (pin "P$1") (pinfunction "1_P$1") (pintype "passive"))
      (node (ref "L12") (pin "P$1") (pinfunction "P$1_P$1") (pintype "bidirectional"))
      (node (ref "Y1") (pin "P$2") (pinfunction "OE_P$2") (pintype "input"))
      (node (ref "Y1") (pin "P$6") (pinfunction "VDD_P$6") (pintype "power_in"))
    )
    (net (code "132") (name "Net-(C98-Pad1)") (class "Default")
      (node (ref "C98") (pin "1") (pinfunction "1_1") (pintype "passive"))
      (node (ref "J2") (pin "VCC") (pinfunction "VCC_VCC") (pintype "power_in"))
      (node (ref "L13") (pin "P$1") (pinfunction "P$1_P$1") (pintype "bidirectional"))
    )
    (net (code "133") (name "Net-(C99-Pad2)") (class "Default")
      (node (ref "C99") (pin "2") (pinfunction "2_2") (pintype "passive"))
      (node (ref "J2") (pin "D+") (pinfunction "D+_D+") (pintype "bidirectional"))
      (node (ref "R60") (pin "1") (pinfunction "1_1") (pintype "passive"))
    )
    (net (code "134") (name "Net-(C100-Pad2)") (class "Default")
      (node (ref "C100") (pin "2") (pinfunction "2_2") (pintype "passive"))
      (node (ref "J2") (pin "D-") (pinfunction "D-_D-") (pintype "bidirectional"))
      (node (ref "R61") (pin "1") (pinfunction "1_1") (pintype "passive"))
    )
    (net (code "135") (name "Net-(C101-2)") (class "Default")
      (node (ref "C101") (pin "P$2") (pinfunction "2_P$2") (pintype "passive"))
      (node (ref "R62") (pin "1") (pinfunction "1_1") (pintype "passive"))
      (node (ref "R63") (pin "1") (pinfunction "1_1") (pintype "passive"))
      (node (ref "U14") (pin "1") (pinfunction "VCCIO_1") (pintype "power_in"))
      (node (ref "U14") (pin "8") (pinfunction "3V3OUT_8") (pintype "output"))
      (node (ref "U14") (pin "9") (pinfunction "~{RESET}_9") (pintype "input"))
    )
    (net (code "136") (name "Net-(C103-2)") (class "Default")
      (node (ref "C103") (pin "P$2") (pinfunction "2_P$2") (pintype "passive"))
      (node (ref "C105") (pin "P$2") (pinfunction "2_P$2") (pintype "passive"))
      (node (ref "L13") (pin "P$2") (pinfunction "P$2_P$2") (pintype "bidirectional"))
      (node (ref "U14") (pin "10") (pinfunction "VCC_10") (pintype "power_in"))
    )
    (net (code "137") (name "Net-(D1-PadANODE)") (class "Default")
      (node (ref "D1") (pin "ANODE") (pinfunction "ANODE_ANODE") (pintype "bidirectional"))
      (node (ref "R38") (pin "2") (pinfunction "2_2") (pintype "passive"))
    )
    (net (code "138") (name "Net-(D2-PadANODE)") (class "Default")
      (node (ref "D2") (pin "ANODE") (pinfunction "ANODE_ANODE") (pintype "bidirectional"))
      (node (ref "R45") (pin "2") (pinfunction "2_2") (pintype "passive"))
    )
    (net (code "139") (name "Net-(D3-PadANODE)") (class "Default")
      (node (ref "D3") (pin "ANODE") (pinfunction "ANODE_ANODE") (pintype "bidirectional"))
      (node (ref "R48") (pin "2") (pinfunction "2_2") (pintype "passive"))
    )
    (net (code "140") (name "Net-(D4-PadANODE)") (class "Default")
      (node (ref "D4") (pin "ANODE") (pinfunction "ANODE_ANODE") (pintype "bidirectional"))
      (node (ref "R49") (pin "2") (pinfunction "2_2") (pintype "passive"))
    )
    (net (code "141") (name "Net-(D5-PadANODE)") (class "Default")
      (node (ref "D5") (pin "ANODE") (pinfunction "ANODE_ANODE") (pintype "bidirectional"))
      (node (ref "R62") (pin "2") (pinfunction "2_2") (pintype "passive"))
    )
    (net (code "142") (name "Net-(D6-PadANODE)") (class "Default")
      (node (ref "D6") (pin "ANODE") (pinfunction "ANODE_ANODE") (pintype "bidirectional"))
      (node (ref "R63") (pin "2") (pinfunction "2_2") (pintype "passive"))
    )
    (net (code "143") (name "Net-(J1-PadP$1)") (class "Default")
      (node (ref "J1") (pin "P$1") (pinfunction "P$1_P$1") (pintype "bidirectional"))
      (node (ref "L1") (pin "P$1") (pinfunction "P$1_P$1") (pintype "bidirectional"))
    )
    (net (code "144") (name "Net-(J1-PadP$2)") (class "Default")
      (node (ref "J1") (pin "P$2") (pinfunction "P$2_P$2") (pintype "bidirectional"))
      (node (ref "L1") (pin "P$2") (pinfunction "P$2_P$2") (pintype "bidirectional"))
    )
    (net (code "145") (name "Net-(R13-Pad2)") (class "Default")
      (node (ref "R13") (pin "2") (pinfunction "2_2") (pintype "passive"))
      (node (ref "S1") (pin "P$2") (pinfunction "P$2_P$2") (pintype "bidirectional"))
    )
    (net (code "146") (name "Net-(R50-Pad1)") (class "Default")
      (node (ref "R50") (pin "1") (pinfunction "1_1") (pintype "passive"))
      (node (ref "R51") (pin "2") (pinfunction "2_2") (pintype "passive"))
      (node (ref "R52") (pin "1") (pinfunction "1_1") (pintype "passive"))
    )
    (net (code "147") (name "Net-(U3-ON)") (class "Default")
      (node (ref "R13") (pin "1") (pinfunction "1_1") (pintype "passive"))
      (node (ref "R15") (pin "2") (pinfunction "2_2") (pintype "passive"))
      (node (ref "U3") (pin "P$10") (pinfunction "ON_P$10") (pintype "input"))
    )
    (net (code "148") (name "Net-(U3-TMR)") (class "Default")
      (node (ref "C9") (pin "1") (pinfunction "1_1") (pintype "passive"))
      (node (ref "U3") (pin "P$8") (pinfunction "TMR_P$8") (pintype "bidirectional"))
    )
    (net (code "149") (name "Net-(U6-SENSE)") (class "Default")
      (node (ref "R29") (pin "1") (pinfunction "1_1") (pintype "passive"))
      (node (ref "R30") (pin "2") (pinfunction "2_2") (pintype "passive"))
      (node (ref "U6") (pin "5") (pinfunction "SENSE_5") (pintype "input"))
    )
    (net (code "150") (name "Net-(U7A-EN)") (class "Default")
      (node (ref "C23") (pin "1") (pinfunction "1_1") (pintype "passive"))
      (node (ref "R27") (pin "2") (pinfunction "2_2") (pintype "passive"))
      (node (ref "R28") (pin "2") (pinfunction "2_2") (pintype "passive"))
      (node (ref "U7") (pin "P$38") (pinfunction "EN_P$38") (pintype "input"))
    )
    (net (code "151") (name "Net-(U7A-FB)") (class "Default")
      (node (ref "C29") (pin "2") (pinfunction "2_2") (pintype "passive"))
      (node (ref "R35") (pin "1") (pinfunction "1_1") (pintype "passive"))
      (node (ref "R37") (pin "2") (pinfunction "2_2") (pintype "passive"))
      (node (ref "U7") (pin "P$1") (pinfunction "FB_P$1") (pintype "input"))
    )
    (net (code "152") (name "Net-(U7A-SW)") (class "Default")
      (node (ref "L8") (pin "P$1") (pinfunction "P$1_P$1") (pintype "bidirectional"))
      (node (ref "U7") (pin "P$3") (pinfunction "SW_P$3") (pintype "bidirectional"))
      (node (ref "U7") (pin "P$4") (pinfunction "SW_P$4") (pintype "bidirectional"))
    )
    (net (code "153") (name "Net-(U7C-EN)") (class "Default")
      (node (ref "C5") (pin "1") (pinfunction "1_1") (pintype "passive"))
      (node (ref "R11") (pin "2") (pinfunction "2_2") (pintype "passive"))
      (node (ref "R12") (pin "1") (pinfunction "1_1") (pintype "passive"))
      (node (ref "U7") (pin "P$14") (pinfunction "EN_P$14") (pintype "input"))
    )
    (net (code "154") (name "Net-(U7C-FB)") (class "Default")
      (node (ref "C11") (pin "2") (pinfunction "2_2") (pintype "passive"))
      (node (ref "R17") (pin "1") (pinfunction "1_1") (pintype "passive"))
      (node (ref "R19") (pin "2") (pinfunction "2_2") (pintype "passive"))
      (node (ref "U7") (pin "P$7") (pinfunction "FB_P$7") (pintype "input"))
    )
    (net (code "155") (name "Net-(U7C-SW)") (class "Default")
      (node (ref "L4") (pin "P$1") (pinfunction "P$1_P$1") (pintype "bidirectional"))
      (node (ref "U7") (pin "P$9") (pinfunction "SW_P$9") (pintype "bidirectional"))
    )
    (net (code "156") (name "Net-(U7D-FB)") (class "Default")
      (node (ref "C27") (pin "2") (pinfunction "2_2") (pintype "passive"))
      (node (ref "R32") (pin "1") (pinfunction "1_1") (pintype "passive"))
      (node (ref "R34") (pin "2") (pinfunction "2_2") (pintype "passive"))
      (node (ref "U7") (pin "P$12") (pinfunction "FB_P$12") (pintype "input"))
    )
    (net (code "157") (name "Net-(U7D-SW)") (class "Default")
      (node (ref "L6") (pin "P$1") (pinfunction "P$1_P$1") (pintype "bidirectional"))
      (node (ref "U7") (pin "P$10") (pinfunction "SW_P$10") (pintype "bidirectional"))
    )
    (net (code "158") (name "Net-(U7E-FB)") (class "Default")
      (node (ref "C14") (pin "2") (pinfunction "2_2") (pintype "passive"))
      (node (ref "R20") (pin "1") (pinfunction "1_1") (pintype "passive"))
      (node (ref "R22") (pin "2") (pinfunction "2_2") (pintype "passive"))
      (node (ref "U7") (pin "P$20") (pinfunction "FB_P$20") (pintype "input"))
    )
    (net (code "159") (name "Net-(U7E-SW)") (class "Default")
      (node (ref "L5") (pin "P$1") (pinfunction "P$1_P$1") (pintype "bidirectional"))
      (node (ref "U7") (pin "P$22") (pinfunction "SW_P$22") (pintype "bidirectional"))
      (node (ref "U7") (pin "P$23") (pinfunction "SW_P$23") (pintype "bidirectional"))
    )
    (net (code "160") (name "Net-(U7G-FB)") (class "Default")
      (node (ref "C28") (pin "2") (pinfunction "2_2") (pintype "passive"))
      (node (ref "R33") (pin "1") (pinfunction "1_1") (pintype "passive"))
      (node (ref "R36") (pin "2") (pinfunction "2_2") (pintype "passive"))
      (node (ref "U7") (pin "P$26") (pinfunction "FB_P$26") (pintype "input"))
    )
    (net (code "161") (name "Net-(U7G-SW)") (class "Default")
      (node (ref "L7") (pin "P$1") (pinfunction "P$1_P$1") (pintype "bidirectional"))
      (node (ref "U7") (pin "P$28") (pinfunction "SW_P$28") (pintype "bidirectional"))
    )
    (net (code "162") (name "Net-(U7H-FB)") (class "Default")
      (node (ref "C10") (pin "2") (pinfunction "2_2") (pintype "passive"))
      (node (ref "R16") (pin "1") (pinfunction "1_1") (pintype "passive"))
      (node (ref "R18") (pin "2") (pinfunction "2_2") (pintype "passive"))
      (node (ref "U7") (pin "P$31") (pinfunction "FB_P$31") (pintype "input"))
    )
    (net (code "163") (name "Net-(U7H-SW)") (class "Default")
      (node (ref "L3") (pin "P$1") (pinfunction "P$1_P$1") (pintype "bidirectional"))
      (node (ref "U7") (pin "P$29") (pinfunction "SW_P$29") (pintype "bidirectional"))
    )
    (net (code "164") (name "Net-(U7I-MODE)") (class "Default")
      (node (ref "R24") (pin "2") (pinfunction "2_2") (pintype "passive"))
      (node (ref "R26") (pin "2") (pinfunction "2_2") (pintype "passive"))
      (node (ref "U7") (pin "P$34") (pinfunction "MODE_P$34") (pintype "input"))
    )
    (net (code "165") (name "Net-(U8-VIN+)") (class "Default")
      (node (ref "U8") (pin "P$16") (pinfunction "VIN+_P$16") (pintype "input"))
      (node (ref "X1") (pin "1") (pinfunction "1_1") (pintype "passive"))
    )
    (net (code "166") (name "Net-(U8-VIN-)") (class "Default")
      (node (ref "R39") (pin "2") (pinfunction "2_2") (pintype "passive"))
      (node (ref "U8") (pin "P$5") (pinfunction "VIN-_P$5") (pintype "input"))
    )
    (net (code "167") (name "Net-(U12-LEA)") (class "Default")
      (node (ref "R46") (pin "2") (pinfunction "2_2") (pintype "passive"))
      (node (ref "R47") (pin "1") (pinfunction "1_1") (pintype "passive"))
      (node (ref "U12") (pin "2") (pinfunction "LEA_2") (pintype "input"))
    )
    (net (code "168") (name "Net-(U12-~{LEA})") (class "Default")
      (node (ref "R42") (pin "2") (pinfunction "2_2") (pintype "passive"))
      (node (ref "R43") (pin "1") (pinfunction "1_1") (pintype "passive"))
      (node (ref "U12") (pin "1") (pinfunction "~{LEA}_1") (pintype "input"))
    )
    (net (code "169") (name "Net-(U13-~{CF})") (class "Default")
      (node (ref "R58") (pin "1") (pinfunction "1_1") (pintype "passive"))
      (node (ref "U13") (pin "P$7") (pinfunction "~{CF}_P$7") (pintype "bidirectional"))
    )
    (net (code "170") (name "Net-(U14-USBDM)") (class "Default")
      (node (ref "R61") (pin "2") (pinfunction "2_2") (pintype "passive"))
      (node (ref "U14") (pin "7") (pinfunction "USBDM_7") (pintype "input"))
    )
    (net (code "171") (name "Net-(U14-USBDP)") (class "Default")
      (node (ref "R60") (pin "2") (pinfunction "2_2") (pintype "passive"))
      (node (ref "U14") (pin "6") (pinfunction "USBDP_6") (pintype "input"))
    )
    (net (code "172") (name "PGOOD") (class "Default")
      (node (ref "R21") (pin "1") (pinfunction "1_1") (pintype "passive"))
      (node (ref "U2") (pin "P$35") (pinfunction "IO_L1P_3_P$35") (pintype "bidirectional"))
      (node (ref "U7") (pin "P$15") (pinfunction "PGOOD_ALL_P$15") (pintype "output"))
    )
    (net (code "173") (name "PROM_TDO") (class "Default")
      (node (ref "U13") (pin "P$17") (pinfunction "TDO_P$17") (pintype "bidirectional"))
      (node (ref "X4") (pin "8") (pinfunction "8_8") (pintype "passive"))
    )
    (net (code "174") (name "PWR_ENABLE") (class "Default")
      (node (ref "TP2") (pin "P$1") (pinfunction "1_P$1") (pintype "bidirectional"))
      (node (ref "U3") (pin "P$3") (pinfunction "EN_P$3") (pintype "output"))
      (node (ref "U7") (pin "P$13") (pinfunction "EN_P$13") (pintype "input"))
      (node (ref "U7") (pin "P$33") (pinfunction "EN_P$33") (pintype "input"))
    )
    (net (code "175") (name "PWR_INT") (class "Default")
      (node (ref "R23") (pin "1") (pinfunction "1_1") (pintype "passive"))
      (node (ref "U2") (pin "P$59") (pinfunction "IO_L13N_D10_2_P$59") (pintype "bidirectional"))
      (node (ref "U3") (pin "P$1") (pinfunction "~{INT}_P$1") (pintype "output"))
    )
    (net (code "176") (name "PWR_KILL") (class "Default")
      (node (ref "R25") (pin "1") (pinfunction "1_1") (pintype "passive"))
      (node (ref "U2") (pin "P$61") (pinfunction "IO_L12N_D2_MISO3_2_P$61") (pintype "bidirectional"))
      (node (ref "U3") (pin "P$9") (pinfunction "~{KILL}_P$9") (pintype "input"))
    )
    (net (code "177") (name "S_TEMP") (class "Default")
      (node (ref "U7") (pin "P$36") (pinfunction "TEMP_P$36") (pintype "output"))
      (node (ref "X3") (pin "P$6") (pinfunction "P$6_P$6") (pintype "bidirectional"))
    )
    (net (code "178") (name "TRIGGER") (class "Default")
      (node (ref "R40") (pin "2") (pinfunction "2_2") (pintype "passive"))
      (node (ref "U12") (pin "3") (pinfunction "+IN_A_3") (pintype "input"))
      (node (ref "X2") (pin "1") (pinfunction "1_1") (pintype "passive"))
    )
    (net (code "179") (name "TRIG_REF") (class "Default")
      (node (ref "TP1") (pin "P$1") (pinfunction "1_P$1") (pintype "bidirectional"))
      (node (ref "U11") (pin "P$1") (pinfunction "VOUT_P$1") (pintype "output"))
      (node (ref "U12") (pin "4") (pinfunction "-IN_A_4") (pintype "input"))
    )
    (net (code "180") (name "TRIG_RESET_HIGH") (class "Default")
      (node (ref "R46") (pin "1") (pinfunction "1_1") (pintype "passive"))
      (node (ref "U2") (pin "P$45") (pinfunction "IO_L49N_D4_2_P$45") (pintype "bidirectional"))
    )
    (net (code "181") (name "TRIG_RESET_LOW") (class "Default")
      (node (ref "R42") (pin "1") (pinfunction "1_1") (pintype "passive"))
      (node (ref "U2") (pin "P$46") (pinfunction "IO_L49P_D3_2_P$46") (pintype "bidirectional"))
    )
    (net (code "182") (name "VIN") (class "Default")
      (node (ref "C1") (pin "1") (pinfunction "1_1") (pintype "passive"))
      (node (ref "C18") (pin "1") (pinfunction "1_1") (pintype "passive"))
      (node (ref "C2") (pin "1") (pinfunction "1_1") (pintype "passive"))
      (node (ref "C20") (pin "1") (pinfunction "1_1") (pintype "passive"))
      (node (ref "C21") (pin "1") (pinfunction "1_1") (pintype "passive"))
      (node (ref "C22") (pin "1") (pinfunction "1_1") (pintype "passive"))
      (node (ref "C3") (pin "1") (pinfunction "1_1") (pintype "passive"))
      (node (ref "C4") (pin "1") (pinfunction "1_1") (pintype "passive"))
      (node (ref "C7") (pin "P$1") (pinfunction "1_P$1") (pintype "passive"))
      (node (ref "C8") (pin "1") (pinfunction "1_1") (pintype "passive"))
      (node (ref "L2") (pin "P$2") (pinfunction "P$2_P$2") (pintype "bidirectional"))
      (node (ref "R26") (pin "1") (pinfunction "1_1") (pintype "passive"))
      (node (ref "S1") (pin "P$3") (pinfunction "P$3_P$3") (pintype "bidirectional"))
      (node (ref "U3") (pin "P$4") (pinfunction "VIN_P$4") (pintype "passive"))
      (node (ref "U3") (pin "P$7") (pinfunction "SEL_P$7") (pintype "input"))
      (node (ref "U7") (pin "P$11") (pinfunction "VIN_P$11") (pintype "power_in"))
      (node (ref "U7") (pin "P$17") (pinfunction "RT_P$17") (pintype "bidirectional"))
      (node (ref "U7") (pin "P$2") (pinfunction "VIN_P$2") (pintype "power_in"))
      (node (ref "U7") (pin "P$21") (pinfunction "VIN_P$21") (pintype "power_in"))
      (node (ref "U7") (pin "P$24") (pinfunction "VIN_P$24") (pintype "power_in"))
      (node (ref "U7") (pin "P$25") (pinfunction "FB_P$25") (pintype "input"))
      (node (ref "U7") (pin "P$27") (pinfunction "VIN_P$27") (pintype "power_in"))
      (node (ref "U7") (pin "P$30") (pinfunction "VIN_P$30") (pintype "power_in"))
      (node (ref "U7") (pin "P$35") (pinfunction "VCC_P$35") (pintype "power_in"))
      (node (ref "U7") (pin "P$5") (pinfunction "VIN_P$5") (pintype "power_in"))
      (node (ref "U7") (pin "P$6") (pinfunction "FB_P$6") (pintype "input"))
      (node (ref "U7") (pin "P$8") (pinfunction "VIN_P$8") (pintype "power_in"))
    )
    (net (code "183") (name "unconnected-(J2-PadID)") (class "Default")
      (node (ref "J2") (pin "ID") (pinfunction "ID_ID") (pintype "bidirectional"))
    )
    (net (code "184") (name "unconnected-(U1A-NC-PadP$52)") (class "Default")
      (node (ref "U1") (pin "P$52") (pinfunction "NC_P$52") (pintype "no_connect"))
    )
    (net (code "185") (name "unconnected-(U1A-NC-PadP$63)") (class "Default")
      (node (ref "U1") (pin "P$63") (pinfunction "NC_P$63") (pintype "no_connect"))
    )
    (net (code "186") (name "unconnected-(U1A-NC-PadP$98)") (class "Default")
      (node (ref "U1") (pin "P$98") (pinfunction "NC_P$98") (pintype "no_connect"))
    )
    (net (code "187") (name "unconnected-(U1A-NC-PadP$109)") (class "Default")
      (node (ref "U1") (pin "P$109") (pinfunction "NC_P$109") (pintype "no_connect"))
    )
    (net (code "188") (name "unconnected-(U1A-NC-PadP$120)") (class "Default")
      (node (ref "U1") (pin "P$120") (pinfunction "NC_P$120") (pintype "no_connect"))
    )
    (net (code "189") (name "unconnected-(U1A-OR+-PadP$79)") (class "Default")
      (node (ref "U1") (pin "P$79") (pinfunction "OR+_P$79") (pintype "output"))
    )
    (net (code "190") (name "unconnected-(U1A-OR--PadP$80)") (class "Default")
      (node (ref "U1") (pin "P$80") (pinfunction "OR-_P$80") (pintype "output"))
    )
    (net (code "191") (name "unconnected-(U2-CMPCS_B_2-PadP$72)") (class "Default")
      (node (ref "U2") (pin "P$72") (pinfunction "CMPCS_B_2_P$72") (pintype "bidirectional"))
    )
    (net (code "192") (name "unconnected-(U3-PGD-PadP$2)") (class "Default")
      (node (ref "U3") (pin "P$2") (pinfunction "PGD_P$2") (pintype "output"))
    )
    (net (code "193") (name "unconnected-(U13-DNC-PadP$2)") (class "Default")
      (node (ref "U13") (pin "P$2") (pinfunction "DNC_P$2") (pintype "no_connect"))
    )
    (net (code "194") (name "unconnected-(U13-DNC-PadP$9)") (class "Default")
      (node (ref "U13") (pin "P$9") (pinfunction "DNC_P$9") (pintype "no_connect"))
    )
    (net (code "195") (name "unconnected-(U13-DNC-PadP$12)") (class "Default")
      (node (ref "U13") (pin "P$12") (pinfunction "DNC_P$12") (pintype "no_connect"))
    )
    (net (code "196") (name "unconnected-(U13-DNC-PadP$14)") (class "Default")
      (node (ref "U13") (pin "P$14") (pinfunction "DNC_P$14") (pintype "no_connect"))
    )
    (net (code "197") (name "unconnected-(U13-DNC-PadP$15)") (class "Default")
      (node (ref "U13") (pin "P$15") (pinfunction "DNC_P$15") (pintype "no_connect"))
    )
    (net (code "198") (name "unconnected-(U13-DNC-PadP$16)") (class "Default")
      (node (ref "U13") (pin "P$16") (pinfunction "DNC_P$16") (pintype "no_connect"))
    )
    (net (code "199") (name "unconnected-(U13-~{CEO}-PadP$13)") (class "Default")
      (node (ref "U13") (pin "P$13") (pinfunction "~{CEO}_P$13") (pintype "bidirectional"))
    )
    (net (code "200") (name "unconnected-(U14-CBUS0-Pad12)") (class "Default")
      (node (ref "U14") (pin "12") (pinfunction "CBUS0_12") (pintype "bidirectional"))
    )
    (net (code "201") (name "unconnected-(U14-CBUS3-Pad14)") (class "Default")
      (node (ref "U14") (pin "14") (pinfunction "CBUS3_14") (pintype "bidirectional"))
    )
    (net (code "202") (name "unconnected-(U14-~{RTS}-Pad16)") (class "Default")
      (node (ref "U14") (pin "16") (pinfunction "~{RTS}_16") (pintype "output"))
    )
    (net (code "203") (name "unconnected-(X4-Pad12)") (class "Default")
      (node (ref "X4") (pin "12") (pinfunction "12_12") (pintype "passive"))
    )
    (net (code "204") (name "unconnected-(X4-Pad14)") (class "Default")
      (node (ref "X4") (pin "14") (pinfunction "14_14") (pintype "passive"))
    )
    (net (code "205") (name "unconnected-(Y1-NC-PadP$1)") (class "Default")
      (node (ref "Y1") (pin "P$1") (pinfunction "NC_P$1") (pintype "no_connect"))
    )
    (net (code "206") (name "unconnected-(Y2-NC-PadP$7)") (class "Default")
      (node (ref "Y2") (pin "P$7") (pinfunction "NC_P$7") (pintype "no_connect"))
    )
    (net (code "207") (name "unconnected-(Y2-NC-PadP$8)") (class "Default")
      (node (ref "Y2") (pin "P$8") (pinfunction "NC_P$8") (pintype "no_connect"))
    )
    (net (code "208") (name "~{PB}") (class "Default")
      (node (ref "U3") (pin "P$5") (pinfunction "~{PB}_P$5") (pintype "input"))
      (node (ref "X3") (pin "P$5") (pinfunction "P$5_P$5") (pintype "bidirectional"))
    )
    (net (code "209") (name "~{RXLED}") (class "Default")
      (node (ref "D5") (pin "CATHODE") (pinfunction "CATHODE_CATHODE") (pintype "bidirectional"))
      (node (ref "U14") (pin "11") (pinfunction "CBUS1_11") (pintype "bidirectional"))
    )
    (net (code "210") (name "~{TXLED}") (class "Default")
      (node (ref "D6") (pin "CATHODE") (pinfunction "CATHODE_CATHODE") (pintype "bidirectional"))
      (node (ref "U14") (pin "5") (pinfunction "CBUS2_5") (pintype "bidirectional"))
    )
  )
)
